# LinTempCont_4ch_V1_0.net
KiCad netlist of a schematic drawn in EAGLE
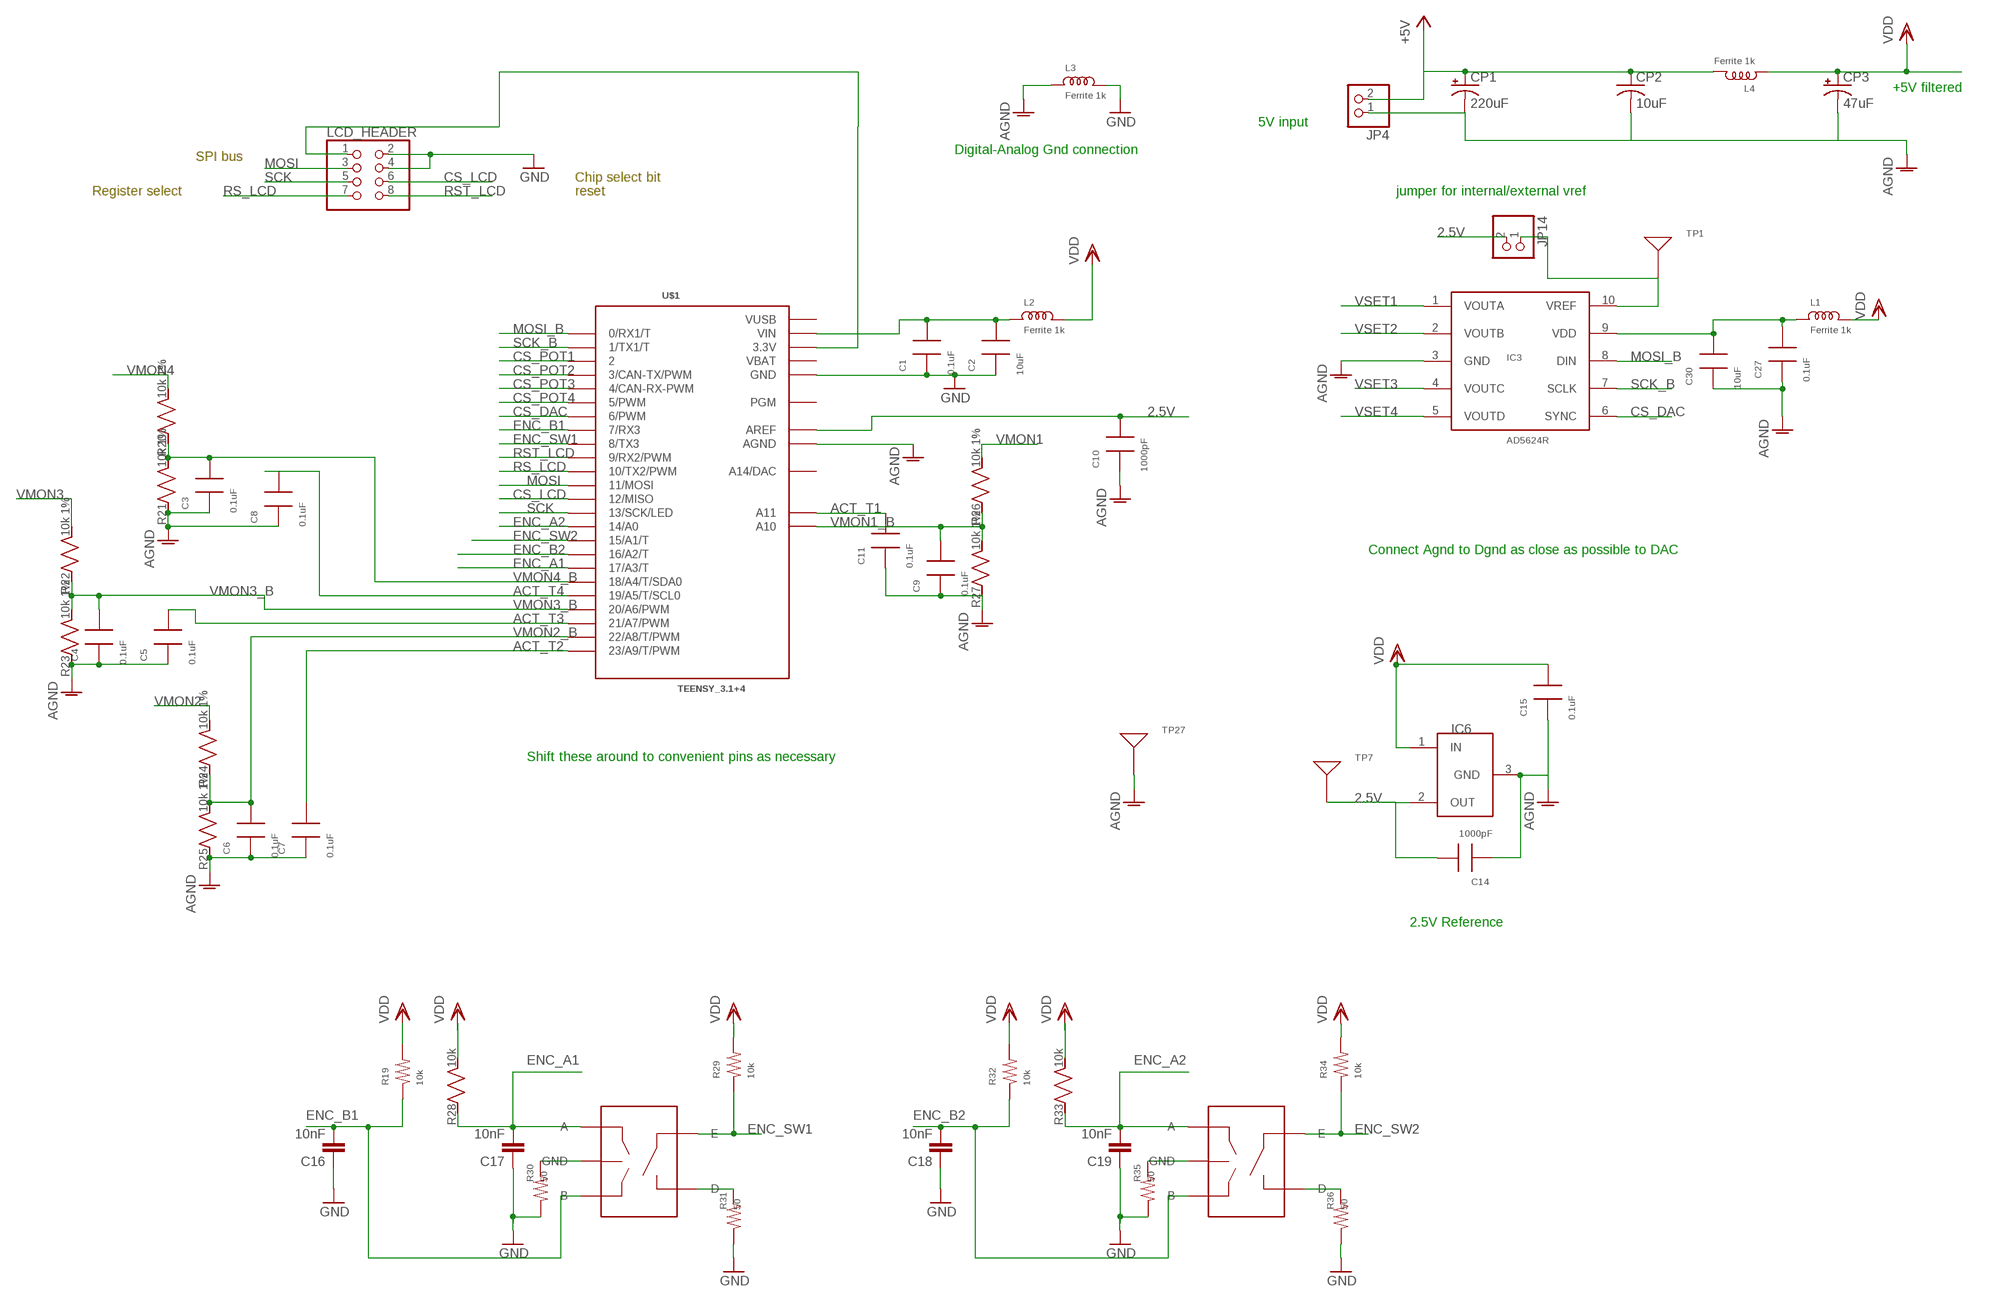
[diagram p0: schematic, sheet 1]
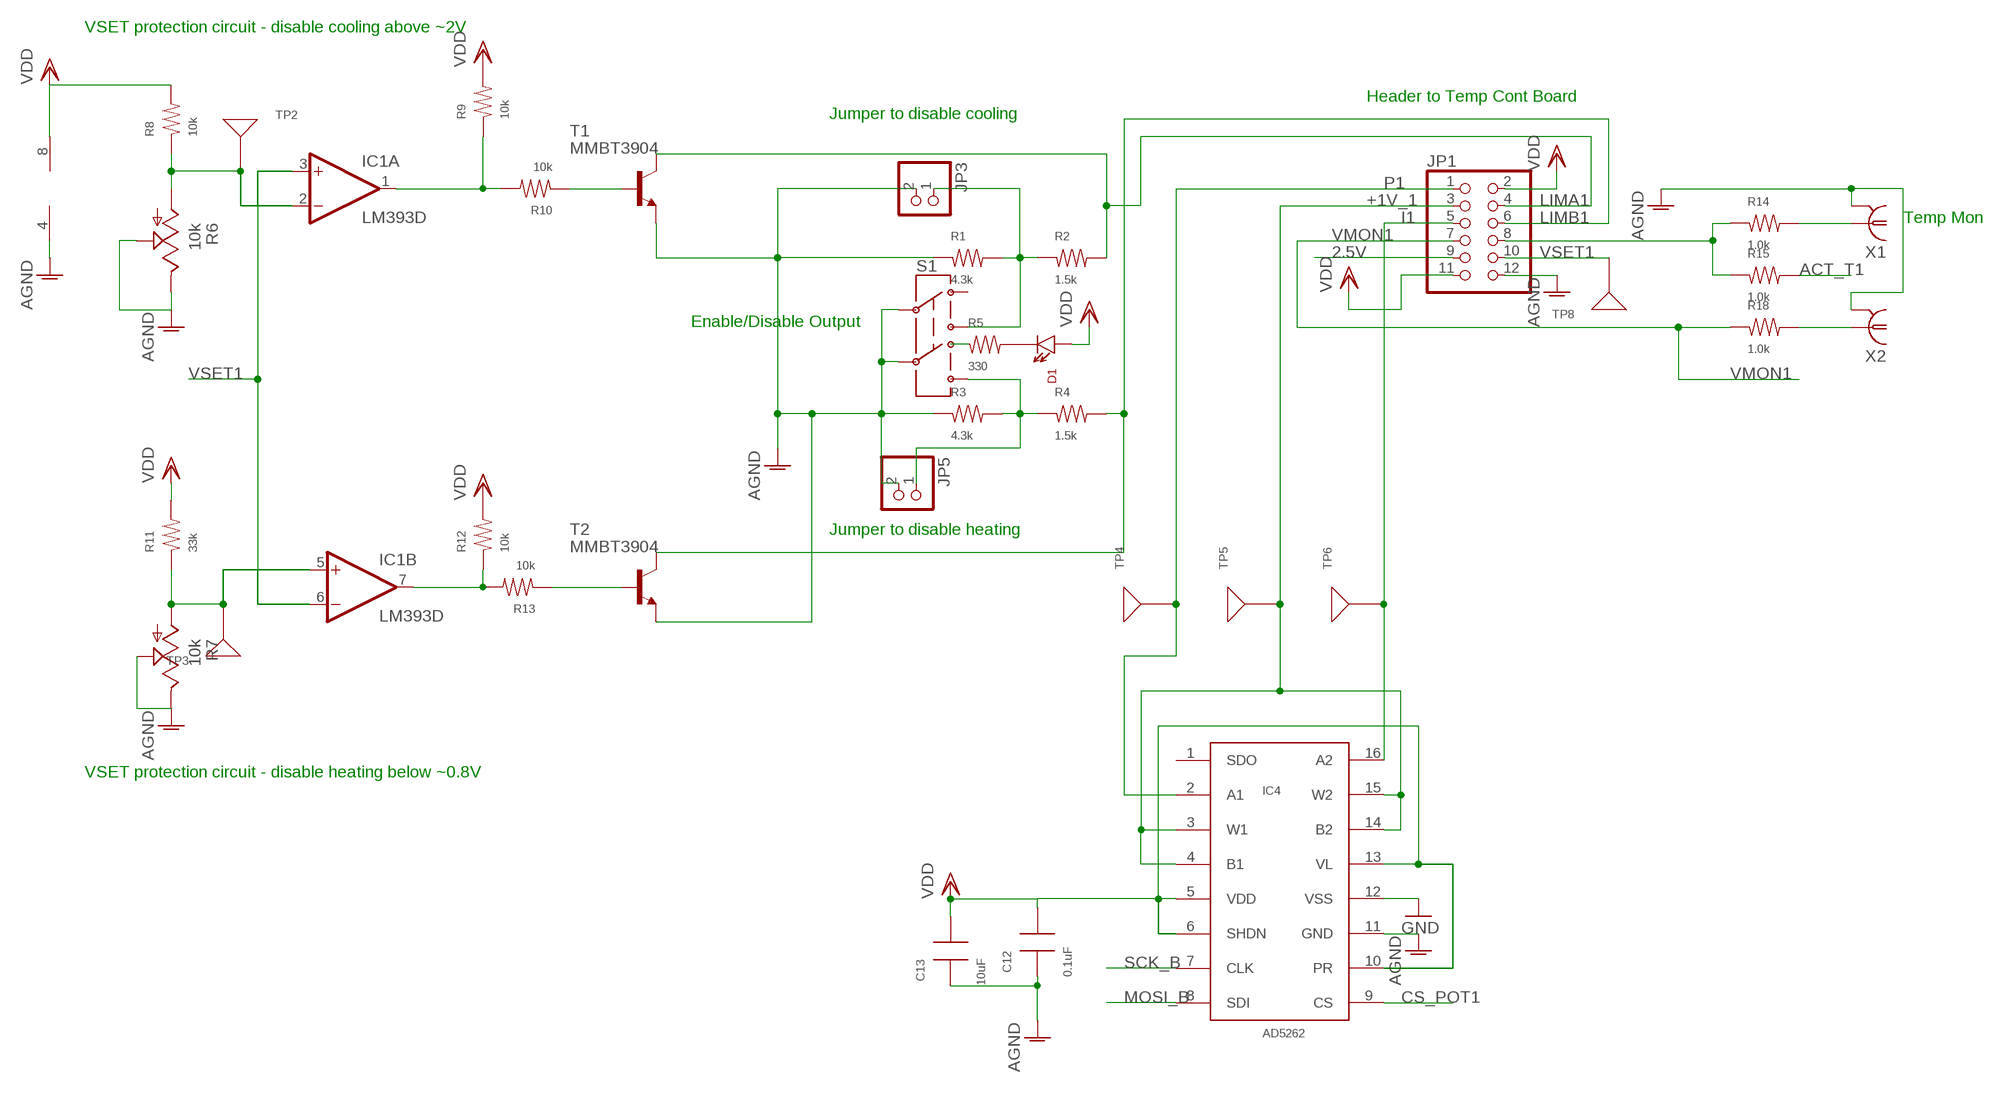
[diagram p1: schematic, sheet 2]
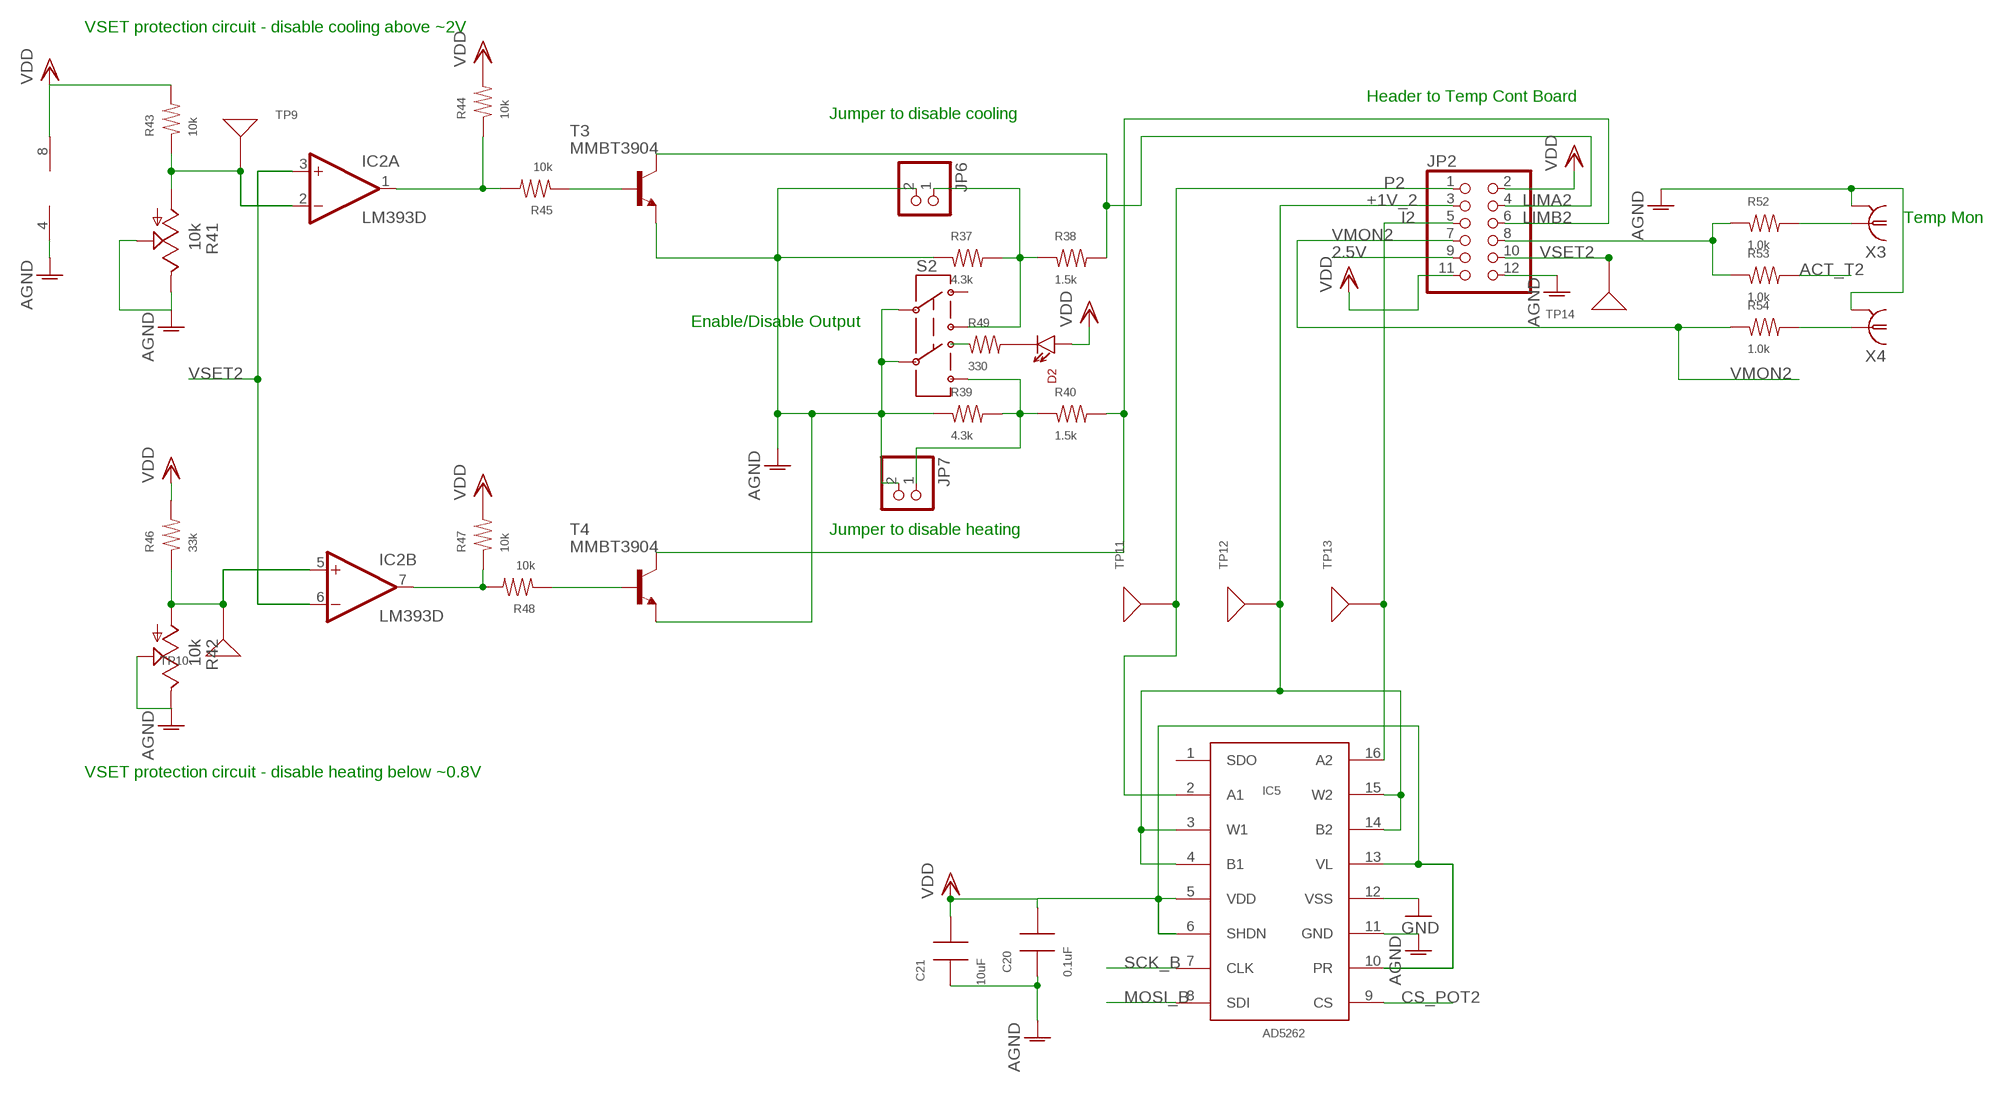
[diagram p2: schematic, sheet 3]
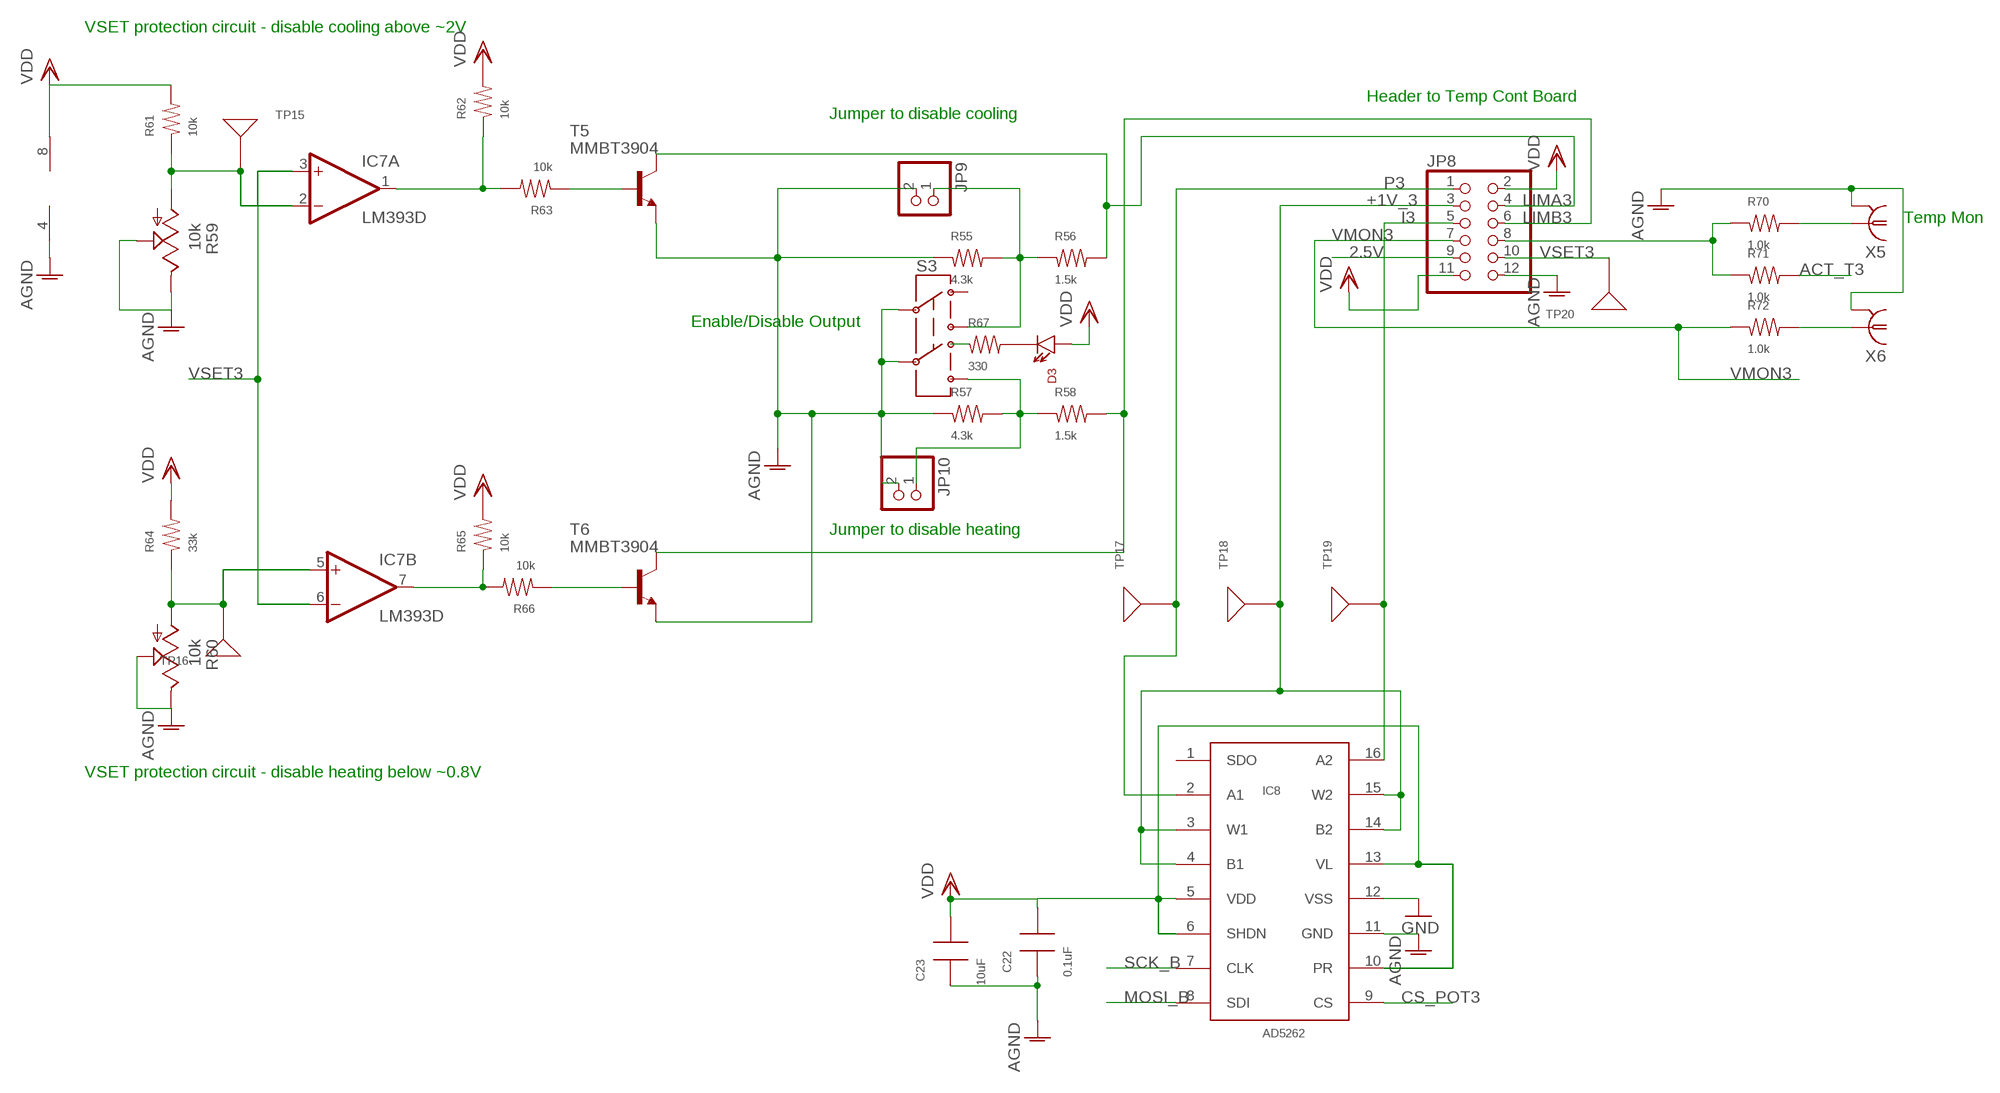
[diagram p3: schematic, sheet 4]
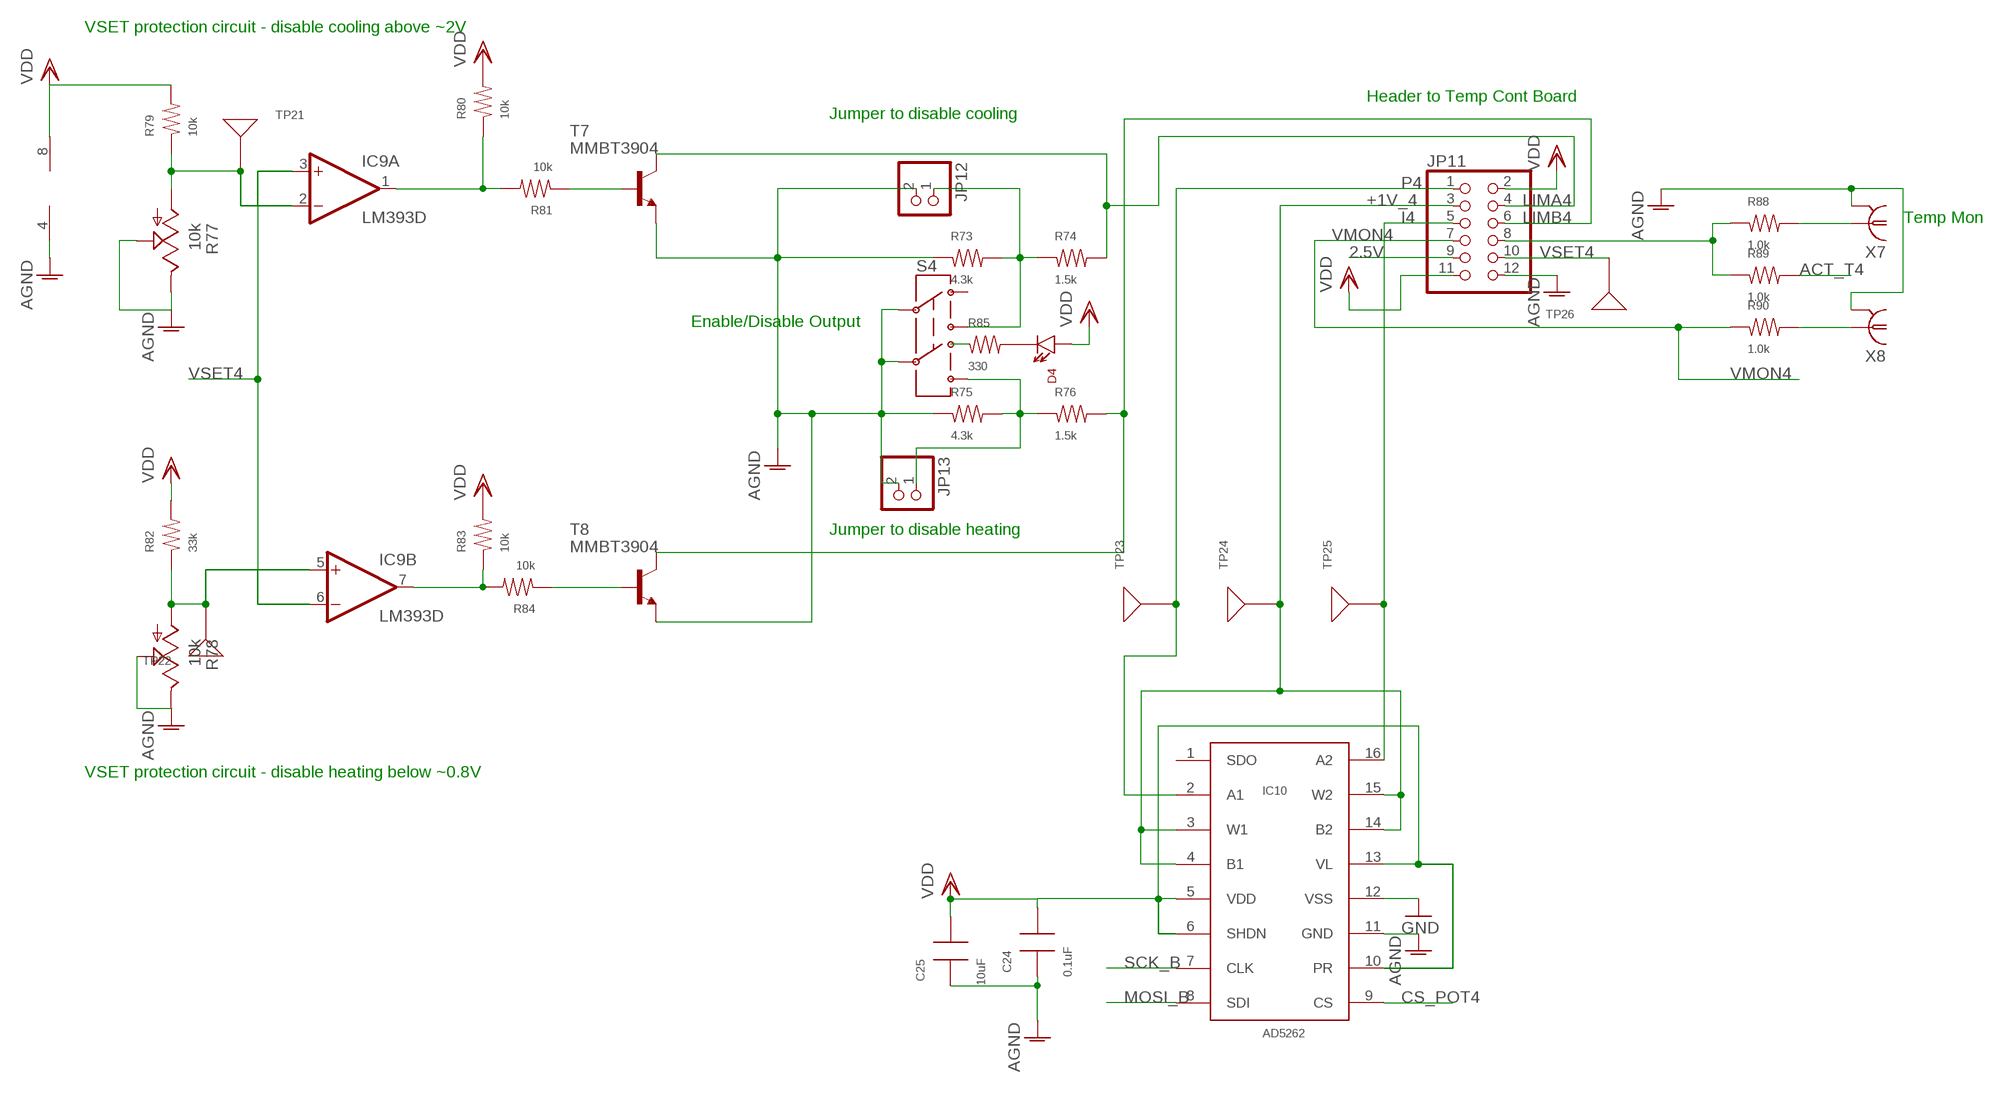
[diagram p4: schematic, sheet 5]

(export (version "E")
  (design (tool "Eeschema 10.0.6"))
  (components
    (comp (ref "C20")
      (value "0.1uF")
      (footprint "eagle-import:0603")
      (libsource (lib "eagle-import") (part "CAP0603"))
    )
    (comp (ref "C21")
      (value "10uF")
      (footprint "eagle-import:0805")
      (libsource (lib "eagle-import") (part "CAP0805"))
    )
    (comp (ref "D2")
      (value "LED/MINI-IND")
      (footprint "eagle-import:HLMP--F0010")
      (libsource (lib "eagle-import") (part "LED/MINI-IND"))
    )
    (comp (ref "IC2")
      (value "LM393D")
      (footprint "eagle-import:SO08")
      (libsource (lib "eagle-import") (part "LM393D"))
    )
    (comp (ref "IC5")
      (value "AD5262")
      (footprint "eagle-import:TSSOP16")
      (libsource (lib "eagle-import") (part "AD5262"))
    )
    (comp (ref "JP2")
      (value "PINHD-2X6/90")
      (footprint "eagle-import:2X06_90")
      (libsource (lib "eagle-import") (part "PINHD-2X6/90"))
    )
    (comp (ref "JP6")
      (value "PINHD-1X2")
      (footprint "eagle-import:1X02")
      (libsource (lib "eagle-import") (part "PINHD-1X2"))
    )
    (comp (ref "JP7")
      (value "PINHD-1X2")
      (footprint "eagle-import:1X02")
      (libsource (lib "eagle-import") (part "PINHD-1X2"))
    )
    (comp (ref "R37")
      (value "4.3k")
      (footprint "eagle-import:0603")
      (libsource (lib "eagle-import") (part "RES0603"))
    )
    (comp (ref "R38")
      (value "1.5k")
      (footprint "eagle-import:0603")
      (libsource (lib "eagle-import") (part "RES0603"))
    )
    (comp (ref "R39")
      (value "4.3k")
      (footprint "eagle-import:0603")
      (libsource (lib "eagle-import") (part "RES0603"))
    )
    (comp (ref "R40")
      (value "1.5k")
      (footprint "eagle-import:0603")
      (libsource (lib "eagle-import") (part "RES0603"))
    )
    (comp (ref "R41")
      (value "10k")
      (footprint "eagle-import:64WPOT")
      (libsource (lib "eagle-import") (part "MODEL64_TRIMPOT/TOP-ADJ"))
    )
    (comp (ref "R42")
      (value "10k")
      (footprint "eagle-import:64WPOT")
      (libsource (lib "eagle-import") (part "MODEL64_TRIMPOT/TOP-ADJ"))
    )
    (comp (ref "R43")
      (value "10k")
      (footprint "eagle-import:0603")
      (libsource (lib "eagle-import") (part "RES0603"))
    )
    (comp (ref "R44")
      (value "10k")
      (footprint "eagle-import:0603")
      (libsource (lib "eagle-import") (part "RES0603"))
    )
    (comp (ref "R45")
      (value "10k")
      (footprint "eagle-import:0603")
      (libsource (lib "eagle-import") (part "RES0603"))
    )
    (comp (ref "R46")
      (value "33k")
      (footprint "eagle-import:0603")
      (libsource (lib "eagle-import") (part "RES0603"))
    )
    (comp (ref "R47")
      (value "10k")
      (footprint "eagle-import:0603")
      (libsource (lib "eagle-import") (part "RES0603"))
    )
    (comp (ref "R48")
      (value "10k")
      (footprint "eagle-import:0603")
      (libsource (lib "eagle-import") (part "RES0603"))
    )
    (comp (ref "R49")
      (value "330")
      (footprint "eagle-import:0603")
      (libsource (lib "eagle-import") (part "RES0603"))
    )
    (comp (ref "R52")
      (value "1.0k")
      (footprint "eagle-import:0603")
      (libsource (lib "eagle-import") (part "RES0603"))
    )
    (comp (ref "R53")
      (value "1.0k")
      (footprint "eagle-import:0603")
      (libsource (lib "eagle-import") (part "RES0603"))
    )
    (comp (ref "R54")
      (value "1.0k")
      (footprint "eagle-import:0603")
      (libsource (lib "eagle-import") (part "RES0603"))
    )
    (comp (ref "S2")
      (value "SWITCH-DPDT/VER")
      (footprint "eagle-import:E-SWITCH-100-M7")
      (libsource (lib "eagle-import") (part "SWITCH-DPDT/VER"))
    )
    (comp (ref "T3")
      (value "MMBT3904")
      (footprint "eagle-import:SOT-23")
      (libsource (lib "eagle-import") (part "MMBT3904"))
    )
    (comp (ref "T4")
      (value "MMBT3904")
      (footprint "eagle-import:SOT-23")
      (libsource (lib "eagle-import") (part "MMBT3904"))
    )
    (comp (ref "TP9")
      (value "TESTPT")
      (footprint "eagle-import:1206TESTPAD")
      (libsource (lib "eagle-import") (part "TESTPT"))
    )
    (comp (ref "TP10")
      (value "TESTPT")
      (footprint "eagle-import:1206TESTPAD")
      (libsource (lib "eagle-import") (part "TESTPT"))
    )
    (comp (ref "TP11")
      (value "TESTPT")
      (footprint "eagle-import:1206TESTPAD")
      (libsource (lib "eagle-import") (part "TESTPT"))
    )
    (comp (ref "TP12")
      (value "TESTPT")
      (footprint "eagle-import:1206TESTPAD")
      (libsource (lib "eagle-import") (part "TESTPT"))
    )
    (comp (ref "TP13")
      (value "TESTPT")
      (footprint "eagle-import:1206TESTPAD")
      (libsource (lib "eagle-import") (part "TESTPT"))
    )
    (comp (ref "TP14")
      (value "TESTPT")
      (footprint "eagle-import:1206TESTPAD")
      (libsource (lib "eagle-import") (part "TESTPT"))
    )
    (comp (ref "X3")
      (value "BNC-H")
      (footprint "eagle-import:BNC90")
      (libsource (lib "eagle-import") (part "BNC-H"))
    )
    (comp (ref "X4")
      (value "BNC-H")
      (footprint "eagle-import:BNC90")
      (libsource (lib "eagle-import") (part "BNC-H"))
    )
    (comp (ref "C22")
      (value "0.1uF")
      (footprint "eagle-import:0603")
      (libsource (lib "eagle-import") (part "CAP0603"))
    )
    (comp (ref "C23")
      (value "10uF")
      (footprint "eagle-import:0805")
      (libsource (lib "eagle-import") (part "CAP0805"))
    )
    (comp (ref "D3")
      (value "LED/MINI-IND")
      (footprint "eagle-import:HLMP--F0010")
      (libsource (lib "eagle-import") (part "LED/MINI-IND"))
    )
    (comp (ref "IC7")
      (value "LM393D")
      (footprint "eagle-import:SO08")
      (libsource (lib "eagle-import") (part "LM393D"))
    )
    (comp (ref "IC8")
      (value "AD5262")
      (footprint "eagle-import:TSSOP16")
      (libsource (lib "eagle-import") (part "AD5262"))
    )
    (comp (ref "JP8")
      (value "PINHD-2X6/90")
      (footprint "eagle-import:2X06_90")
      (libsource (lib "eagle-import") (part "PINHD-2X6/90"))
    )
    (comp (ref "JP9")
      (value "PINHD-1X2")
      (footprint "eagle-import:1X02")
      (libsource (lib "eagle-import") (part "PINHD-1X2"))
    )
    (comp (ref "JP10")
      (value "PINHD-1X2")
      (footprint "eagle-import:1X02")
      (libsource (lib "eagle-import") (part "PINHD-1X2"))
    )
    (comp (ref "R55")
      (value "4.3k")
      (footprint "eagle-import:0603")
      (libsource (lib "eagle-import") (part "RES0603"))
    )
    (comp (ref "R56")
      (value "1.5k")
      (footprint "eagle-import:0603")
      (libsource (lib "eagle-import") (part "RES0603"))
    )
    (comp (ref "R57")
      (value "4.3k")
      (footprint "eagle-import:0603")
      (libsource (lib "eagle-import") (part "RES0603"))
    )
    (comp (ref "R58")
      (value "1.5k")
      (footprint "eagle-import:0603")
      (libsource (lib "eagle-import") (part "RES0603"))
    )
    (comp (ref "R59")
      (value "10k")
      (footprint "eagle-import:64WPOT")
      (libsource (lib "eagle-import") (part "MODEL64_TRIMPOT/TOP-ADJ"))
    )
    (comp (ref "R60")
      (value "10k")
      (footprint "eagle-import:64WPOT")
      (libsource (lib "eagle-import") (part "MODEL64_TRIMPOT/TOP-ADJ"))
    )
    (comp (ref "R61")
      (value "10k")
      (footprint "eagle-import:0603")
      (libsource (lib "eagle-import") (part "RES0603"))
    )
    (comp (ref "R62")
      (value "10k")
      (footprint "eagle-import:0603")
      (libsource (lib "eagle-import") (part "RES0603"))
    )
    (comp (ref "R63")
      (value "10k")
      (footprint "eagle-import:0603")
      (libsource (lib "eagle-import") (part "RES0603"))
    )
    (comp (ref "R64")
      (value "33k")
      (footprint "eagle-import:0603")
      (libsource (lib "eagle-import") (part "RES0603"))
    )
    (comp (ref "R65")
      (value "10k")
      (footprint "eagle-import:0603")
      (libsource (lib "eagle-import") (part "RES0603"))
    )
    (comp (ref "R66")
      (value "10k")
      (footprint "eagle-import:0603")
      (libsource (lib "eagle-import") (part "RES0603"))
    )
    (comp (ref "R67")
      (value "330")
      (footprint "eagle-import:0603")
      (libsource (lib "eagle-import") (part "RES0603"))
    )
    (comp (ref "R70")
      (value "1.0k")
      (footprint "eagle-import:0603")
      (libsource (lib "eagle-import") (part "RES0603"))
    )
    (comp (ref "R71")
      (value "1.0k")
      (footprint "eagle-import:0603")
      (libsource (lib "eagle-import") (part "RES0603"))
    )
    (comp (ref "R72")
      (value "1.0k")
      (footprint "eagle-import:0603")
      (libsource (lib "eagle-import") (part "RES0603"))
    )
    (comp (ref "S3")
      (value "SWITCH-DPDT/VER")
      (footprint "eagle-import:E-SWITCH-100-M7")
      (libsource (lib "eagle-import") (part "SWITCH-DPDT/VER"))
    )
    (comp (ref "T5")
      (value "MMBT3904")
      (footprint "eagle-import:SOT-23")
      (libsource (lib "eagle-import") (part "MMBT3904"))
    )
    (comp (ref "T6")
      (value "MMBT3904")
      (footprint "eagle-import:SOT-23")
      (libsource (lib "eagle-import") (part "MMBT3904"))
    )
    (comp (ref "TP15")
      (value "TESTPT")
      (footprint "eagle-import:1206TESTPAD")
      (libsource (lib "eagle-import") (part "TESTPT"))
    )
    (comp (ref "TP16")
      (value "TESTPT")
      (footprint "eagle-import:1206TESTPAD")
      (libsource (lib "eagle-import") (part "TESTPT"))
    )
    (comp (ref "TP17")
      (value "TESTPT")
      (footprint "eagle-import:1206TESTPAD")
      (libsource (lib "eagle-import") (part "TESTPT"))
    )
    (comp (ref "TP18")
      (value "TESTPT")
      (footprint "eagle-import:1206TESTPAD")
      (libsource (lib "eagle-import") (part "TESTPT"))
    )
    (comp (ref "TP19")
      (value "TESTPT")
      (footprint "eagle-import:1206TESTPAD")
      (libsource (lib "eagle-import") (part "TESTPT"))
    )
    (comp (ref "TP20")
      (value "TESTPT")
      (footprint "eagle-import:1206TESTPAD")
      (libsource (lib "eagle-import") (part "TESTPT"))
    )
    (comp (ref "X5")
      (value "BNC-H")
      (footprint "eagle-import:BNC90")
      (libsource (lib "eagle-import") (part "BNC-H"))
    )
    (comp (ref "X6")
      (value "BNC-H")
      (footprint "eagle-import:BNC90")
      (libsource (lib "eagle-import") (part "BNC-H"))
    )
    (comp (ref "C1")
      (value "0.1uF")
      (footprint "eagle-import:0603")
      (libsource (lib "eagle-import") (part "CAP0603"))
    )
    (comp (ref "C2")
      (value "10uF")
      (footprint "eagle-import:0805")
      (libsource (lib "eagle-import") (part "CAP0805"))
    )
    (comp (ref "C3")
      (value "0.1uF")
      (footprint "eagle-import:0603")
      (libsource (lib "eagle-import") (part "CAP0603"))
    )
    (comp (ref "C4")
      (value "0.1uF")
      (footprint "eagle-import:0603")
      (libsource (lib "eagle-import") (part "CAP0603"))
    )
    (comp (ref "C5")
      (value "0.1uF")
      (footprint "eagle-import:0603")
      (libsource (lib "eagle-import") (part "CAP0603"))
    )
    (comp (ref "C6")
      (value "0.1uF")
      (footprint "eagle-import:0603")
      (libsource (lib "eagle-import") (part "CAP0603"))
    )
    (comp (ref "C7")
      (value "0.1uF")
      (footprint "eagle-import:0603")
      (libsource (lib "eagle-import") (part "CAP0603"))
    )
    (comp (ref "C8")
      (value "0.1uF")
      (footprint "eagle-import:0603")
      (libsource (lib "eagle-import") (part "CAP0603"))
    )
    (comp (ref "C9")
      (value "0.1uF")
      (footprint "eagle-import:0603")
      (libsource (lib "eagle-import") (part "CAP0603"))
    )
    (comp (ref "C10")
      (value "1000pF")
      (footprint "eagle-import:0603")
      (libsource (lib "eagle-import") (part "CAP0603"))
    )
    (comp (ref "C11")
      (value "0.1uF")
      (footprint "eagle-import:0603")
      (libsource (lib "eagle-import") (part "CAP0603"))
    )
    (comp (ref "C14")
      (value "1000pF")
      (footprint "eagle-import:0603")
      (libsource (lib "eagle-import") (part "CAP0603"))
    )
    (comp (ref "C15")
      (value "0.1uF")
      (footprint "eagle-import:0603")
      (libsource (lib "eagle-import") (part "CAP0603"))
    )
    (comp (ref "C16")
      (value "10nF")
      (footprint "eagle-import:C0603")
      (libsource (lib "eagle-import") (part "C-EUC0603"))
    )
    (comp (ref "C17")
      (value "10nF")
      (footprint "eagle-import:C0603")
      (libsource (lib "eagle-import") (part "C-EUC0603"))
    )
    (comp (ref "C18")
      (value "10nF")
      (footprint "eagle-import:C0603")
      (libsource (lib "eagle-import") (part "C-EUC0603"))
    )
    (comp (ref "C19")
      (value "10nF")
      (footprint "eagle-import:C0603")
      (libsource (lib "eagle-import") (part "C-EUC0603"))
    )
    (comp (ref "C27")
      (value "0.1uF")
      (footprint "eagle-import:0603")
      (libsource (lib "eagle-import") (part "CAP0603"))
    )
    (comp (ref "C30")
      (value "10uF")
      (footprint "eagle-import:0805")
      (libsource (lib "eagle-import") (part "CAP0805"))
    )
    (comp (ref "CP1")
      (value "220uF")
      (footprint "eagle-import:PANASONIC_F")
      (libsource (lib "eagle-import") (part "CPOL-USF"))
    )
    (comp (ref "CP2")
      (value "10uF")
      (footprint "eagle-import:C0805K")
      (libsource (lib "eagle-import") (part "C-USC0805K"))
    )
    (comp (ref "CP3")
      (value "47uF")
      (footprint "eagle-import:CT7343")
      (libsource (lib "eagle-import") (part "CPOL-USCT7343"))
    )
    (comp (ref "ENC1")
      (value "PEC09")
      (footprint "eagle-import:PEC092320FS")
      (libsource (lib "eagle-import") (part "PEC09"))
    )
    (comp (ref "ENC2")
      (value "PEC09")
      (footprint "eagle-import:PEC092320FS")
      (libsource (lib "eagle-import") (part "PEC09"))
    )
    (comp (ref "IC3")
      (value "AD5624R")
      (footprint "eagle-import:MSOP10")
      (libsource (lib "eagle-import") (part "AD5624R"))
    )
    (comp (ref "IC6")
      (value "TS6001")
      (footprint "eagle-import:SOT-23")
      (libsource (lib "eagle-import") (part "TS6001"))
    )
    (comp (ref "JP4")
      (value "SCRWTRM-1X2")
      (footprint "eagle-import:1X02_SCRWTRM")
      (libsource (lib "eagle-import") (part "SCRWTRM-1X2"))
    )
    (comp (ref "JP14")
      (value "PINHD-1X2")
      (footprint "eagle-import:1X02")
      (libsource (lib "eagle-import") (part "PINHD-1X2"))
    )
    (comp (ref "L1")
      (value "Ferrite 1k")
      (footprint "eagle-import:0805")
      (libsource (lib "eagle-import") (part "INDUCTOR-0805"))
    )
    (comp (ref "L2")
      (value "Ferrite 1k")
      (footprint "eagle-import:0805")
      (libsource (lib "eagle-import") (part "INDUCTOR-0805"))
    )
    (comp (ref "L3")
      (value "Ferrite 1k")
      (footprint "eagle-import:0805")
      (libsource (lib "eagle-import") (part "INDUCTOR-0805"))
    )
    (comp (ref "L4")
      (value "Ferrite 1k")
      (footprint "eagle-import:0805")
      (libsource (lib "eagle-import") (part "INDUCTOR-0805"))
    )
    (comp (ref "LCD_HEADER")
      (value "PINHD-2X4-SHROUD")
      (footprint "eagle-import:ML08")
      (libsource (lib "eagle-import") (part "PINHD-2X4-SHROUD"))
    )
    (comp (ref "R19")
      (value "10k")
      (footprint "eagle-import:0603")
      (libsource (lib "eagle-import") (part "RES0603"))
    )
    (comp (ref "R20")
      (value "10k 1%")
      (footprint "eagle-import:R_0603")
      (libsource (lib "eagle-import") (part "R_SMDR0603"))
    )
    (comp (ref "R21")
      (value "10k 1%")
      (footprint "eagle-import:R_0603")
      (libsource (lib "eagle-import") (part "R_SMDR0603"))
    )
    (comp (ref "R22")
      (value "10k 1%")
      (footprint "eagle-import:R_0603")
      (libsource (lib "eagle-import") (part "R_SMDR0603"))
    )
    (comp (ref "R23")
      (value "10k 1%")
      (footprint "eagle-import:R_0603")
      (libsource (lib "eagle-import") (part "R_SMDR0603"))
    )
    (comp (ref "R24")
      (value "10k 1%")
      (footprint "eagle-import:R_0603")
      (libsource (lib "eagle-import") (part "R_SMDR0603"))
    )
    (comp (ref "R25")
      (value "10k 1%")
      (footprint "eagle-import:R_0603")
      (libsource (lib "eagle-import") (part "R_SMDR0603"))
    )
    (comp (ref "R26")
      (value "10k 1%")
      (footprint "eagle-import:R_0603")
      (libsource (lib "eagle-import") (part "R_SMDR0603"))
    )
    (comp (ref "R27")
      (value "10k 1%")
      (footprint "eagle-import:R_0603")
      (libsource (lib "eagle-import") (part "R_SMDR0603"))
    )
    (comp (ref "R28")
      (value "10k")
      (footprint "eagle-import:R_0603")
      (libsource (lib "eagle-import") (part "R_SMDR0603"))
    )
    (comp (ref "R29")
      (value "10k")
      (footprint "eagle-import:0603")
      (libsource (lib "eagle-import") (part "RES0603"))
    )
    (comp (ref "R30")
      (value "50")
      (footprint "eagle-import:0603")
      (libsource (lib "eagle-import") (part "RES0603"))
    )
    (comp (ref "R31")
      (value "50")
      (footprint "eagle-import:0603")
      (libsource (lib "eagle-import") (part "RES0603"))
    )
    (comp (ref "R32")
      (value "10k")
      (footprint "eagle-import:0603")
      (libsource (lib "eagle-import") (part "RES0603"))
    )
    (comp (ref "R33")
      (value "10k")
      (footprint "eagle-import:R_0603")
      (libsource (lib "eagle-import") (part "R_SMDR0603"))
    )
    (comp (ref "R34")
      (value "10k")
      (footprint "eagle-import:0603")
      (libsource (lib "eagle-import") (part "RES0603"))
    )
    (comp (ref "R35")
      (value "50")
      (footprint "eagle-import:0603")
      (libsource (lib "eagle-import") (part "RES0603"))
    )
    (comp (ref "R36")
      (value "50")
      (footprint "eagle-import:0603")
      (libsource (lib "eagle-import") (part "RES0603"))
    )
    (comp (ref "TP1")
      (value "TESTPT")
      (footprint "eagle-import:1206TESTPAD")
      (libsource (lib "eagle-import") (part "TESTPT"))
    )
    (comp (ref "TP7")
      (value "TESTPT")
      (footprint "eagle-import:1206TESTPAD")
      (libsource (lib "eagle-import") (part "TESTPT"))
    )
    (comp (ref "TP27")
      (value "TESTPT")
      (footprint "eagle-import:1206TESTPAD")
      (libsource (lib "eagle-import") (part "TESTPT"))
    )
    (comp (ref "U$1")
      (value "TEENSY_3.1+4")
      (footprint "eagle-import:TEENSY_3.1+4")
      (libsource (lib "eagle-import") (part "TEENSY_3.1+4"))
    )
    (comp (ref "C12")
      (value "0.1uF")
      (footprint "eagle-import:0603")
      (libsource (lib "eagle-import") (part "CAP0603"))
    )
    (comp (ref "C13")
      (value "10uF")
      (footprint "eagle-import:0805")
      (libsource (lib "eagle-import") (part "CAP0805"))
    )
    (comp (ref "D1")
      (value "LED/MINI-IND")
      (footprint "eagle-import:HLMP--F0010")
      (libsource (lib "eagle-import") (part "LED/MINI-IND"))
    )
    (comp (ref "IC1")
      (value "LM393D")
      (footprint "eagle-import:SO08")
      (libsource (lib "eagle-import") (part "LM393D"))
    )
    (comp (ref "IC4")
      (value "AD5262")
      (footprint "eagle-import:TSSOP16")
      (libsource (lib "eagle-import") (part "AD5262"))
    )
    (comp (ref "JP1")
      (value "PINHD-2X6/90")
      (footprint "eagle-import:2X06_90")
      (libsource (lib "eagle-import") (part "PINHD-2X6/90"))
    )
    (comp (ref "JP3")
      (value "PINHD-1X2")
      (footprint "eagle-import:1X02")
      (libsource (lib "eagle-import") (part "PINHD-1X2"))
    )
    (comp (ref "JP5")
      (value "PINHD-1X2")
      (footprint "eagle-import:1X02")
      (libsource (lib "eagle-import") (part "PINHD-1X2"))
    )
    (comp (ref "R1")
      (value "4.3k")
      (footprint "eagle-import:0603")
      (libsource (lib "eagle-import") (part "RES0603"))
    )
    (comp (ref "R2")
      (value "1.5k")
      (footprint "eagle-import:0603")
      (libsource (lib "eagle-import") (part "RES0603"))
    )
    (comp (ref "R3")
      (value "4.3k")
      (footprint "eagle-import:0603")
      (libsource (lib "eagle-import") (part "RES0603"))
    )
    (comp (ref "R4")
      (value "1.5k")
      (footprint "eagle-import:0603")
      (libsource (lib "eagle-import") (part "RES0603"))
    )
    (comp (ref "R5")
      (value "330")
      (footprint "eagle-import:0603")
      (libsource (lib "eagle-import") (part "RES0603"))
    )
    (comp (ref "R6")
      (value "10k")
      (footprint "eagle-import:64WPOT")
      (libsource (lib "eagle-import") (part "MODEL64_TRIMPOT/TOP-ADJ"))
    )
    (comp (ref "R7")
      (value "10k")
      (footprint "eagle-import:64WPOT")
      (libsource (lib "eagle-import") (part "MODEL64_TRIMPOT/TOP-ADJ"))
    )
    (comp (ref "R8")
      (value "10k")
      (footprint "eagle-import:0603")
      (libsource (lib "eagle-import") (part "RES0603"))
    )
    (comp (ref "R9")
      (value "10k")
      (footprint "eagle-import:0603")
      (libsource (lib "eagle-import") (part "RES0603"))
    )
    (comp (ref "R10")
      (value "10k")
      (footprint "eagle-import:0603")
      (libsource (lib "eagle-import") (part "RES0603"))
    )
    (comp (ref "R11")
      (value "33k")
      (footprint "eagle-import:0603")
      (libsource (lib "eagle-import") (part "RES0603"))
    )
    (comp (ref "R12")
      (value "10k")
      (footprint "eagle-import:0603")
      (libsource (lib "eagle-import") (part "RES0603"))
    )
    (comp (ref "R13")
      (value "10k")
      (footprint "eagle-import:0603")
      (libsource (lib "eagle-import") (part "RES0603"))
    )
    (comp (ref "R14")
      (value "1.0k")
      (footprint "eagle-import:0603")
      (libsource (lib "eagle-import") (part "RES0603"))
    )
    (comp (ref "R15")
      (value "1.0k")
      (footprint "eagle-import:0603")
      (libsource (lib "eagle-import") (part "RES0603"))
    )
    (comp (ref "R18")
      (value "1.0k")
      (footprint "eagle-import:0603")
      (libsource (lib "eagle-import") (part "RES0603"))
    )
    (comp (ref "S1")
      (value "SWITCH-DPDT/VER")
      (footprint "eagle-import:E-SWITCH-100-M7")
      (libsource (lib "eagle-import") (part "SWITCH-DPDT/VER"))
    )
    (comp (ref "T1")
      (value "MMBT3904")
      (footprint "eagle-import:SOT-23")
      (libsource (lib "eagle-import") (part "MMBT3904"))
    )
    (comp (ref "T2")
      (value "MMBT3904")
      (footprint "eagle-import:SOT-23")
      (libsource (lib "eagle-import") (part "MMBT3904"))
    )
    (comp (ref "TP2")
      (value "TESTPT")
      (footprint "eagle-import:1206TESTPAD")
      (libsource (lib "eagle-import") (part "TESTPT"))
    )
    (comp (ref "TP3")
      (value "TESTPT")
      (footprint "eagle-import:1206TESTPAD")
      (libsource (lib "eagle-import") (part "TESTPT"))
    )
    (comp (ref "TP4")
      (value "TESTPT")
      (footprint "eagle-import:1206TESTPAD")
      (libsource (lib "eagle-import") (part "TESTPT"))
    )
    (comp (ref "TP5")
      (value "TESTPT")
      (footprint "eagle-import:1206TESTPAD")
      (libsource (lib "eagle-import") (part "TESTPT"))
    )
    (comp (ref "TP6")
      (value "TESTPT")
      (footprint "eagle-import:1206TESTPAD")
      (libsource (lib "eagle-import") (part "TESTPT"))
    )
    (comp (ref "TP8")
      (value "TESTPT")
      (footprint "eagle-import:1206TESTPAD")
      (libsource (lib "eagle-import") (part "TESTPT"))
    )
    (comp (ref "X1")
      (value "BNC-H")
      (footprint "eagle-import:BNC90")
      (libsource (lib "eagle-import") (part "BNC-H"))
    )
    (comp (ref "X2")
      (value "BNC-H")
      (footprint "eagle-import:BNC90")
      (libsource (lib "eagle-import") (part "BNC-H"))
    )
    (comp (ref "C24")
      (value "0.1uF")
      (footprint "eagle-import:0603")
      (libsource (lib "eagle-import") (part "CAP0603"))
    )
    (comp (ref "C25")
      (value "10uF")
      (footprint "eagle-import:0805")
      (libsource (lib "eagle-import") (part "CAP0805"))
    )
    (comp (ref "D4")
      (value "LED/MINI-IND")
      (footprint "eagle-import:HLMP--F0010")
      (libsource (lib "eagle-import") (part "LED/MINI-IND"))
    )
    (comp (ref "IC9")
      (value "LM393D")
      (footprint "eagle-import:SO08")
      (libsource (lib "eagle-import") (part "LM393D"))
    )
    (comp (ref "IC10")
      (value "AD5262")
      (footprint "eagle-import:TSSOP16")
      (libsource (lib "eagle-import") (part "AD5262"))
    )
    (comp (ref "JP11")
      (value "PINHD-2X6/90")
      (footprint "eagle-import:2X06_90")
      (libsource (lib "eagle-import") (part "PINHD-2X6/90"))
    )
    (comp (ref "JP12")
      (value "PINHD-1X2")
      (footprint "eagle-import:1X02")
      (libsource (lib "eagle-import") (part "PINHD-1X2"))
    )
    (comp (ref "JP13")
      (value "PINHD-1X2")
      (footprint "eagle-import:1X02")
      (libsource (lib "eagle-import") (part "PINHD-1X2"))
    )
    (comp (ref "R73")
      (value "4.3k")
      (footprint "eagle-import:0603")
      (libsource (lib "eagle-import") (part "RES0603"))
    )
    (comp (ref "R74")
      (value "1.5k")
      (footprint "eagle-import:0603")
      (libsource (lib "eagle-import") (part "RES0603"))
    )
    (comp (ref "R75")
      (value "4.3k")
      (footprint "eagle-import:0603")
      (libsource (lib "eagle-import") (part "RES0603"))
    )
    (comp (ref "R76")
      (value "1.5k")
      (footprint "eagle-import:0603")
      (libsource (lib "eagle-import") (part "RES0603"))
    )
    (comp (ref "R77")
      (value "10k")
      (footprint "eagle-import:64WPOT")
      (libsource (lib "eagle-import") (part "MODEL64_TRIMPOT/TOP-ADJ"))
    )
    (comp (ref "R78")
      (value "10k")
      (footprint "eagle-import:64WPOT")
      (libsource (lib "eagle-import") (part "MODEL64_TRIMPOT/TOP-ADJ"))
    )
    (comp (ref "R79")
      (value "10k")
      (footprint "eagle-import:0603")
      (libsource (lib "eagle-import") (part "RES0603"))
    )
    (comp (ref "R80")
      (value "10k")
      (footprint "eagle-import:0603")
      (libsource (lib "eagle-import") (part "RES0603"))
    )
    (comp (ref "R81")
      (value "10k")
      (footprint "eagle-import:0603")
      (libsource (lib "eagle-import") (part "RES0603"))
    )
    (comp (ref "R82")
      (value "33k")
      (footprint "eagle-import:0603")
      (libsource (lib "eagle-import") (part "RES0603"))
    )
    (comp (ref "R83")
      (value "10k")
      (footprint "eagle-import:0603")
      (libsource (lib "eagle-import") (part "RES0603"))
    )
    (comp (ref "R84")
      (value "10k")
      (footprint "eagle-import:0603")
      (libsource (lib "eagle-import") (part "RES0603"))
    )
    (comp (ref "R85")
      (value "330")
      (footprint "eagle-import:0603")
      (libsource (lib "eagle-import") (part "RES0603"))
    )
    (comp (ref "R88")
      (value "1.0k")
      (footprint "eagle-import:0603")
      (libsource (lib "eagle-import") (part "RES0603"))
    )
    (comp (ref "R89")
      (value "1.0k")
      (footprint "eagle-import:0603")
      (libsource (lib "eagle-import") (part "RES0603"))
    )
    (comp (ref "R90")
      (value "1.0k")
      (footprint "eagle-import:0603")
      (libsource (lib "eagle-import") (part "RES0603"))
    )
    (comp (ref "S4")
      (value "SWITCH-DPDT/VER")
      (footprint "eagle-import:E-SWITCH-100-M7")
      (libsource (lib "eagle-import") (part "SWITCH-DPDT/VER"))
    )
    (comp (ref "T7")
      (value "MMBT3904")
      (footprint "eagle-import:SOT-23")
      (libsource (lib "eagle-import") (part "MMBT3904"))
    )
    (comp (ref "T8")
      (value "MMBT3904")
      (footprint "eagle-import:SOT-23")
      (libsource (lib "eagle-import") (part "MMBT3904"))
    )
    (comp (ref "TP21")
      (value "TESTPT")
      (footprint "eagle-import:1206TESTPAD")
      (libsource (lib "eagle-import") (part "TESTPT"))
    )
    (comp (ref "TP22")
      (value "TESTPT")
      (footprint "eagle-import:1206TESTPAD")
      (libsource (lib "eagle-import") (part "TESTPT"))
    )
    (comp (ref "TP23")
      (value "TESTPT")
      (footprint "eagle-import:1206TESTPAD")
      (libsource (lib "eagle-import") (part "TESTPT"))
    )
    (comp (ref "TP24")
      (value "TESTPT")
      (footprint "eagle-import:1206TESTPAD")
      (libsource (lib "eagle-import") (part "TESTPT"))
    )
    (comp (ref "TP25")
      (value "TESTPT")
      (footprint "eagle-import:1206TESTPAD")
      (libsource (lib "eagle-import") (part "TESTPT"))
    )
    (comp (ref "TP26")
      (value "TESTPT")
      (footprint "eagle-import:1206TESTPAD")
      (libsource (lib "eagle-import") (part "TESTPT"))
    )
    (comp (ref "X7")
      (value "BNC-H")
      (footprint "eagle-import:BNC90")
      (libsource (lib "eagle-import") (part "BNC-H"))
    )
    (comp (ref "X8")
      (value "BNC-H")
      (footprint "eagle-import:BNC90")
      (libsource (lib "eagle-import") (part "BNC-H"))
    )
  )
  (nets
    (net (code "1") (name "+1V_1") (class "Default")
      (node (ref "IC4") (pin "14") (pinfunction "B2_14") (pintype "bidirectional"))
      (node (ref "IC4") (pin "15") (pinfunction "W2_15") (pintype "bidirectional"))
      (node (ref "IC4") (pin "3") (pinfunction "W1_3") (pintype "bidirectional"))
      (node (ref "IC4") (pin "4") (pinfunction "B1_4") (pintype "bidirectional"))
      (node (ref "JP1") (pin "3") (pinfunction "3_3") (pintype "passive"))
      (node (ref "TP5") (pin "P$1") (pinfunction "P$1_P$1") (pintype "bidirectional"))
    )
    (net (code "2") (name "+1V_2") (class "Default")
      (node (ref "IC5") (pin "14") (pinfunction "B2_14") (pintype "bidirectional"))
      (node (ref "IC5") (pin "15") (pinfunction "W2_15") (pintype "bidirectional"))
      (node (ref "IC5") (pin "3") (pinfunction "W1_3") (pintype "bidirectional"))
      (node (ref "IC5") (pin "4") (pinfunction "B1_4") (pintype "bidirectional"))
      (node (ref "JP2") (pin "3") (pinfunction "3_3") (pintype "passive"))
      (node (ref "TP12") (pin "P$1") (pinfunction "P$1_P$1") (pintype "bidirectional"))
    )
    (net (code "3") (name "+1V_3") (class "Default")
      (node (ref "IC8") (pin "14") (pinfunction "B2_14") (pintype "bidirectional"))
      (node (ref "IC8") (pin "15") (pinfunction "W2_15") (pintype "bidirectional"))
      (node (ref "IC8") (pin "3") (pinfunction "W1_3") (pintype "bidirectional"))
      (node (ref "IC8") (pin "4") (pinfunction "B1_4") (pintype "bidirectional"))
      (node (ref "JP8") (pin "3") (pinfunction "3_3") (pintype "passive"))
      (node (ref "TP18") (pin "P$1") (pinfunction "P$1_P$1") (pintype "bidirectional"))
    )
    (net (code "4") (name "+1V_4") (class "Default")
      (node (ref "IC10") (pin "14") (pinfunction "B2_14") (pintype "bidirectional"))
      (node (ref "IC10") (pin "15") (pinfunction "W2_15") (pintype "bidirectional"))
      (node (ref "IC10") (pin "3") (pinfunction "W1_3") (pintype "bidirectional"))
      (node (ref "IC10") (pin "4") (pinfunction "B1_4") (pintype "bidirectional"))
      (node (ref "JP11") (pin "3") (pinfunction "3_3") (pintype "passive"))
      (node (ref "TP24") (pin "P$1") (pinfunction "P$1_P$1") (pintype "bidirectional"))
    )
    (net (code "5") (name "+5V") (class "Default")
      (node (ref "CP1") (pin "+") (pinfunction "+_+") (pintype "passive"))
      (node (ref "CP2") (pin "1") (pinfunction "1_1") (pintype "passive"))
      (node (ref "JP4") (pin "2") (pinfunction "2_2") (pintype "passive"))
      (node (ref "L4") (pin "2") (pinfunction "P$2_2") (pintype "passive"))
    )
    (net (code "6") (name "2.5V") (class "Default")
      (node (ref "C10") (pin "2") (pinfunction "P$2_2") (pintype "passive"))
      (node (ref "C14") (pin "2") (pinfunction "P$2_2") (pintype "passive"))
      (node (ref "IC6") (pin "2") (pinfunction "OUT_2") (pintype "bidirectional"))
      (node (ref "JP1") (pin "9") (pinfunction "9_9") (pintype "passive"))
      (node (ref "JP11") (pin "9") (pinfunction "9_9") (pintype "passive"))
      (node (ref "JP14") (pin "2") (pinfunction "2_2") (pintype "passive"))
      (node (ref "JP2") (pin "9") (pinfunction "9_9") (pintype "passive"))
      (node (ref "JP8") (pin "9") (pinfunction "9_9") (pintype "passive"))
      (node (ref "TP7") (pin "P$1") (pinfunction "P$1_P$1") (pintype "bidirectional"))
      (node (ref "U$1") (pin "AREF") (pinfunction "AREF_AREF") (pintype "power_in"))
    )
    (net (code "7") (name "ACT_T1") (class "Default")
      (node (ref "C11") (pin "2") (pinfunction "P$2_2") (pintype "passive"))
      (node (ref "R15") (pin "2") (pinfunction "P$2_2") (pintype "passive"))
      (node (ref "U$1") (pin "A11") (pinfunction "A11_A11") (pintype "bidirectional"))
    )
    (net (code "8") (name "ACT_T2") (class "Default")
      (node (ref "C7") (pin "2") (pinfunction "P$2_2") (pintype "passive"))
      (node (ref "R53") (pin "2") (pinfunction "P$2_2") (pintype "passive"))
      (node (ref "U$1") (pin "23/A9") (pinfunction "23/A9/T/PWM_23/A9") (pintype "bidirectional"))
    )
    (net (code "9") (name "ACT_T3") (class "Default")
      (node (ref "C5") (pin "2") (pinfunction "P$2_2") (pintype "passive"))
      (node (ref "R71") (pin "2") (pinfunction "P$2_2") (pintype "passive"))
      (node (ref "U$1") (pin "21/A7") (pinfunction "21/A7/PWM_21/A7") (pintype "bidirectional"))
    )
    (net (code "10") (name "ACT_T4") (class "Default")
      (node (ref "C8") (pin "2") (pinfunction "P$2_2") (pintype "passive"))
      (node (ref "R89") (pin "2") (pinfunction "P$2_2") (pintype "passive"))
      (node (ref "U$1") (pin "19/A5") (pinfunction "19/A5/T/SCL0_19/A5") (pintype "bidirectional"))
    )
    (net (code "11") (name "AGND") (class "Default")
      (node (ref "C10") (pin "1") (pinfunction "P$1_1") (pintype "passive"))
      (node (ref "C11") (pin "1") (pinfunction "P$1_1") (pintype "passive"))
      (node (ref "C12") (pin "1") (pinfunction "P$1_1") (pintype "passive"))
      (node (ref "C13") (pin "1") (pinfunction "P$1_1") (pintype "passive"))
      (node (ref "C14") (pin "1") (pinfunction "P$1_1") (pintype "passive"))
      (node (ref "C15") (pin "1") (pinfunction "P$1_1") (pintype "passive"))
      (node (ref "C20") (pin "1") (pinfunction "P$1_1") (pintype "passive"))
      (node (ref "C21") (pin "1") (pinfunction "P$1_1") (pintype "passive"))
      (node (ref "C22") (pin "1") (pinfunction "P$1_1") (pintype "passive"))
      (node (ref "C23") (pin "1") (pinfunction "P$1_1") (pintype "passive"))
      (node (ref "C24") (pin "1") (pinfunction "P$1_1") (pintype "passive"))
      (node (ref "C25") (pin "1") (pinfunction "P$1_1") (pintype "passive"))
      (node (ref "C27") (pin "1") (pinfunction "P$1_1") (pintype "passive"))
      (node (ref "C3") (pin "1") (pinfunction "P$1_1") (pintype "passive"))
      (node (ref "C30") (pin "1") (pinfunction "P$1_1") (pintype "passive"))
      (node (ref "C4") (pin "1") (pinfunction "P$1_1") (pintype "passive"))
      (node (ref "C5") (pin "1") (pinfunction "P$1_1") (pintype "passive"))
      (node (ref "C6") (pin "1") (pinfunction "P$1_1") (pintype "passive"))
      (node (ref "C7") (pin "1") (pinfunction "P$1_1") (pintype "passive"))
      (node (ref "C8") (pin "1") (pinfunction "P$1_1") (pintype "passive"))
      (node (ref "C9") (pin "1") (pinfunction "P$1_1") (pintype "passive"))
      (node (ref "CP1") (pin "-") (pinfunction "-_-") (pintype "passive"))
      (node (ref "CP2") (pin "2") (pinfunction "2_2") (pintype "passive"))
      (node (ref "CP3") (pin "-") (pinfunction "-_-") (pintype "passive"))
      (node (ref "IC1") (pin "4") (pinfunction "V-_4") (pintype "power_in"))
      (node (ref "IC10") (pin "11") (pinfunction "GND_11") (pintype "power_in"))
      (node (ref "IC2") (pin "4") (pinfunction "V-_4") (pintype "power_in"))
      (node (ref "IC3") (pin "3") (pinfunction "GND_3") (pintype "power_in"))
      (node (ref "IC4") (pin "11") (pinfunction "GND_11") (pintype "power_in"))
      (node (ref "IC5") (pin "11") (pinfunction "GND_11") (pintype "power_in"))
      (node (ref "IC6") (pin "3") (pinfunction "GND_3") (pintype "bidirectional"))
      (node (ref "IC7") (pin "4") (pinfunction "V-_4") (pintype "power_in"))
      (node (ref "IC8") (pin "11") (pinfunction "GND_11") (pintype "power_in"))
      (node (ref "IC9") (pin "4") (pinfunction "V-_4") (pintype "power_in"))
      (node (ref "JP1") (pin "12") (pinfunction "12_12") (pintype "passive"))
      (node (ref "JP10") (pin "2") (pinfunction "2_2") (pintype "passive"))
      (node (ref "JP11") (pin "12") (pinfunction "12_12") (pintype "passive"))
      (node (ref "JP12") (pin "2") (pinfunction "2_2") (pintype "passive"))
      (node (ref "JP13") (pin "2") (pinfunction "2_2") (pintype "passive"))
      (node (ref "JP2") (pin "12") (pinfunction "12_12") (pintype "passive"))
      (node (ref "JP3") (pin "2") (pinfunction "2_2") (pintype "passive"))
      (node (ref "JP4") (pin "1") (pinfunction "1_1") (pintype "passive"))
      (node (ref "JP5") (pin "2") (pinfunction "2_2") (pintype "passive"))
      (node (ref "JP6") (pin "2") (pinfunction "2_2") (pintype "passive"))
      (node (ref "JP7") (pin "2") (pinfunction "2_2") (pintype "passive"))
      (node (ref "JP8") (pin "12") (pinfunction "12_12") (pintype "passive"))
      (node (ref "JP9") (pin "2") (pinfunction "2_2") (pintype "passive"))
      (node (ref "L3") (pin "1") (pinfunction "P$1_1") (pintype "passive"))
      (node (ref "R1") (pin "1") (pinfunction "P$1_1") (pintype "passive"))
      (node (ref "R21") (pin "P$1") (pinfunction "1_P$1") (pintype "passive"))
      (node (ref "R23") (pin "P$1") (pinfunction "1_P$1") (pintype "passive"))
      (node (ref "R25") (pin "P$1") (pinfunction "1_P$1") (pintype "passive"))
      (node (ref "R27") (pin "P$1") (pinfunction "1_P$1") (pintype "passive"))
      (node (ref "R3") (pin "1") (pinfunction "P$1_1") (pintype "passive"))
      (node (ref "R37") (pin "1") (pinfunction "P$1_1") (pintype "passive"))
      (node (ref "R39") (pin "1") (pinfunction "P$1_1") (pintype "passive"))
      (node (ref "R41") (pin "P$2") (pinfunction "2_P$2") (pintype "passive"))
      (node (ref "R41") (pin "P$3") (pinfunction "3_P$3") (pintype "passive"))
      (node (ref "R42") (pin "P$2") (pinfunction "2_P$2") (pintype "passive"))
      (node (ref "R42") (pin "P$3") (pinfunction "3_P$3") (pintype "passive"))
      (node (ref "R55") (pin "1") (pinfunction "P$1_1") (pintype "passive"))
      (node (ref "R57") (pin "1") (pinfunction "P$1_1") (pintype "passive"))
      (node (ref "R59") (pin "P$2") (pinfunction "2_P$2") (pintype "passive"))
      (node (ref "R59") (pin "P$3") (pinfunction "3_P$3") (pintype "passive"))
      (node (ref "R6") (pin "P$2") (pinfunction "2_P$2") (pintype "passive"))
      (node (ref "R6") (pin "P$3") (pinfunction "3_P$3") (pintype "passive"))
      (node (ref "R60") (pin "P$2") (pinfunction "2_P$2") (pintype "passive"))
      (node (ref "R60") (pin "P$3") (pinfunction "3_P$3") (pintype "passive"))
      (node (ref "R7") (pin "P$2") (pinfunction "2_P$2") (pintype "passive"))
      (node (ref "R7") (pin "P$3") (pinfunction "3_P$3") (pintype "passive"))
      (node (ref "R73") (pin "1") (pinfunction "P$1_1") (pintype "passive"))
      (node (ref "R75") (pin "1") (pinfunction "P$1_1") (pintype "passive"))
      (node (ref "R77") (pin "P$2") (pinfunction "2_P$2") (pintype "passive"))
      (node (ref "R77") (pin "P$3") (pinfunction "3_P$3") (pintype "passive"))
      (node (ref "R78") (pin "P$2") (pinfunction "2_P$2") (pintype "passive"))
      (node (ref "R78") (pin "P$3") (pinfunction "3_P$3") (pintype "passive"))
      (node (ref "S1") (pin "P$2") (pinfunction "2_P$2") (pintype "bidirectional"))
      (node (ref "S1") (pin "P$5") (pinfunction "5_P$5") (pintype "bidirectional"))
      (node (ref "S2") (pin "P$2") (pinfunction "2_P$2") (pintype "bidirectional"))
      (node (ref "S2") (pin "P$5") (pinfunction "5_P$5") (pintype "bidirectional"))
      (node (ref "S3") (pin "P$2") (pinfunction "2_P$2") (pintype "bidirectional"))
      (node (ref "S3") (pin "P$5") (pinfunction "5_P$5") (pintype "bidirectional"))
      (node (ref "S4") (pin "P$2") (pinfunction "2_P$2") (pintype "bidirectional"))
      (node (ref "S4") (pin "P$5") (pinfunction "5_P$5") (pintype "bidirectional"))
      (node (ref "T1") (pin "2") (pinfunction "E_2") (pintype "passive"))
      (node (ref "T2") (pin "2") (pinfunction "E_2") (pintype "passive"))
      (node (ref "T3") (pin "2") (pinfunction "E_2") (pintype "passive"))
      (node (ref "T4") (pin "2") (pinfunction "E_2") (pintype "passive"))
      (node (ref "T5") (pin "2") (pinfunction "E_2") (pintype "passive"))
      (node (ref "T6") (pin "2") (pinfunction "E_2") (pintype "passive"))
      (node (ref "T7") (pin "2") (pinfunction "E_2") (pintype "passive"))
      (node (ref "T8") (pin "2") (pinfunction "E_2") (pintype "passive"))
      (node (ref "TP27") (pin "P$1") (pinfunction "P$1_P$1") (pintype "bidirectional"))
      (node (ref "U$1") (pin "AGND") (pinfunction "AGND_AGND") (pintype "power_in"))
      (node (ref "X1") (pin "2") (pinfunction "2_2") (pintype "passive"))
      (node (ref "X2") (pin "2") (pinfunction "2_2") (pintype "passive"))
      (node (ref "X3") (pin "2") (pinfunction "2_2") (pintype "passive"))
      (node (ref "X4") (pin "2") (pinfunction "2_2") (pintype "passive"))
      (node (ref "X5") (pin "2") (pinfunction "2_2") (pintype "passive"))
      (node (ref "X6") (pin "2") (pinfunction "2_2") (pintype "passive"))
      (node (ref "X7") (pin "2") (pinfunction "2_2") (pintype "passive"))
      (node (ref "X8") (pin "2") (pinfunction "2_2") (pintype "passive"))
    )
    (net (code "12") (name "CS_DAC") (class "Default")
      (node (ref "IC3") (pin "6") (pinfunction "SYNC_6") (pintype "bidirectional"))
      (node (ref "U$1") (pin "6") (pinfunction "6/PWM_6") (pintype "bidirectional"))
    )
    (net (code "13") (name "CS_LCD") (class "Default")
      (node (ref "LCD_HEADER") (pin "6") (pinfunction "6_6") (pintype "passive"))
      (node (ref "U$1") (pin "12") (pinfunction "12/MISO_12") (pintype "bidirectional"))
    )
    (net (code "14") (name "CS_POT1") (class "Default")
      (node (ref "IC4") (pin "9") (pinfunction "CS_9") (pintype "bidirectional"))
      (node (ref "U$1") (pin "2") (pinfunction "2_2") (pintype "bidirectional"))
    )
    (net (code "15") (name "CS_POT2") (class "Default")
      (node (ref "IC5") (pin "9") (pinfunction "CS_9") (pintype "bidirectional"))
      (node (ref "U$1") (pin "3") (pinfunction "3/CAN-TX/PWM_3") (pintype "bidirectional"))
    )
    (net (code "16") (name "CS_POT3") (class "Default")
      (node (ref "IC8") (pin "9") (pinfunction "CS_9") (pintype "bidirectional"))
      (node (ref "U$1") (pin "4") (pinfunction "4/CAN-RX-PWM_4") (pintype "bidirectional"))
    )
    (net (code "17") (name "CS_POT4") (class "Default")
      (node (ref "IC10") (pin "9") (pinfunction "CS_9") (pintype "bidirectional"))
      (node (ref "U$1") (pin "5") (pinfunction "5/PWM_5") (pintype "bidirectional"))
    )
    (net (code "18") (name "ENC_A1") (class "Default")
      (node (ref "C17") (pin "2") (pinfunction "2_2") (pintype "passive"))
      (node (ref "ENC1") (pin "A") (pinfunction "A_A") (pintype "bidirectional"))
      (node (ref "R28") (pin "P$1") (pinfunction "1_P$1") (pintype "passive"))
      (node (ref "U$1") (pin "17/A3") (pinfunction "17/A3/T_17/A3") (pintype "bidirectional"))
    )
    (net (code "19") (name "ENC_A2") (class "Default")
      (node (ref "C19") (pin "2") (pinfunction "2_2") (pintype "passive"))
      (node (ref "ENC2") (pin "A") (pinfunction "A_A") (pintype "bidirectional"))
      (node (ref "R33") (pin "P$1") (pinfunction "1_P$1") (pintype "passive"))
      (node (ref "U$1") (pin "14/A0") (pinfunction "14/A0_14/A0") (pintype "bidirectional"))
    )
    (net (code "20") (name "ENC_B1") (class "Default")
      (node (ref "C16") (pin "2") (pinfunction "2_2") (pintype "passive"))
      (node (ref "ENC1") (pin "B") (pinfunction "B_B") (pintype "bidirectional"))
      (node (ref "R19") (pin "1") (pinfunction "P$1_1") (pintype "passive"))
      (node (ref "U$1") (pin "7") (pinfunction "7/RX3_7") (pintype "bidirectional"))
    )
    (net (code "21") (name "ENC_B2") (class "Default")
      (node (ref "C18") (pin "2") (pinfunction "2_2") (pintype "passive"))
      (node (ref "ENC2") (pin "B") (pinfunction "B_B") (pintype "bidirectional"))
      (node (ref "R32") (pin "1") (pinfunction "P$1_1") (pintype "passive"))
      (node (ref "U$1") (pin "16/A2") (pinfunction "16/A2/T_16/A2") (pintype "bidirectional"))
    )
    (net (code "22") (name "ENC_SW1") (class "Default")
      (node (ref "ENC1") (pin "E") (pinfunction "E_E") (pintype "bidirectional"))
      (node (ref "R29") (pin "1") (pinfunction "P$1_1") (pintype "passive"))
      (node (ref "U$1") (pin "8") (pinfunction "8/TX3_8") (pintype "bidirectional"))
    )
    (net (code "23") (name "ENC_SW2") (class "Default")
      (node (ref "ENC2") (pin "E") (pinfunction "E_E") (pintype "bidirectional"))
      (node (ref "R34") (pin "1") (pinfunction "P$1_1") (pintype "passive"))
      (node (ref "U$1") (pin "15/A1") (pinfunction "15/A1/T_15/A1") (pintype "bidirectional"))
    )
    (net (code "24") (name "GND") (class "Default")
      (node (ref "C1") (pin "1") (pinfunction "P$1_1") (pintype "passive"))
      (node (ref "C16") (pin "1") (pinfunction "1_1") (pintype "passive"))
      (node (ref "C17") (pin "1") (pinfunction "1_1") (pintype "passive"))
      (node (ref "C18") (pin "1") (pinfunction "1_1") (pintype "passive"))
      (node (ref "C19") (pin "1") (pinfunction "1_1") (pintype "passive"))
      (node (ref "C2") (pin "1") (pinfunction "P$1_1") (pintype "passive"))
      (node (ref "IC10") (pin "12") (pinfunction "VSS_12") (pintype "power_in"))
      (node (ref "IC4") (pin "12") (pinfunction "VSS_12") (pintype "power_in"))
      (node (ref "IC5") (pin "12") (pinfunction "VSS_12") (pintype "power_in"))
      (node (ref "IC8") (pin "12") (pinfunction "VSS_12") (pintype "power_in"))
      (node (ref "L3") (pin "2") (pinfunction "P$2_2") (pintype "passive"))
      (node (ref "LCD_HEADER") (pin "2") (pinfunction "2_2") (pintype "passive"))
      (node (ref "LCD_HEADER") (pin "4") (pinfunction "4_4") (pintype "passive"))
      (node (ref "R30") (pin "1") (pinfunction "P$1_1") (pintype "passive"))
      (node (ref "R31") (pin "1") (pinfunction "P$1_1") (pintype "passive"))
      (node (ref "R35") (pin "1") (pinfunction "P$1_1") (pintype "passive"))
      (node (ref "R36") (pin "1") (pinfunction "P$1_1") (pintype "passive"))
      (node (ref "U$1") (pin "GND") (pinfunction "GND_GND") (pintype "power_in"))
      (node (ref "U$1") (pin "GND1") (pinfunction "GND_GND1") (pintype "power_in"))
    )
    (net (code "25") (name "I1") (class "Default")
      (node (ref "IC4") (pin "16") (pinfunction "A2_16") (pintype "bidirectional"))
      (node (ref "JP1") (pin "5") (pinfunction "5_5") (pintype "passive"))
      (node (ref "TP6") (pin "P$1") (pinfunction "P$1_P$1") (pintype "bidirectional"))
    )
    (net (code "26") (name "I2") (class "Default")
      (node (ref "IC5") (pin "16") (pinfunction "A2_16") (pintype "bidirectional"))
      (node (ref "JP2") (pin "5") (pinfunction "5_5") (pintype "passive"))
      (node (ref "TP13") (pin "P$1") (pinfunction "P$1_P$1") (pintype "bidirectional"))
    )
    (net (code "27") (name "I3") (class "Default")
      (node (ref "IC8") (pin "16") (pinfunction "A2_16") (pintype "bidirectional"))
      (node (ref "JP8") (pin "5") (pinfunction "5_5") (pintype "passive"))
      (node (ref "TP19") (pin "P$1") (pinfunction "P$1_P$1") (pintype "bidirectional"))
    )
    (net (code "28") (name "I4") (class "Default")
      (node (ref "IC10") (pin "16") (pinfunction "A2_16") (pintype "bidirectional"))
      (node (ref "JP11") (pin "5") (pinfunction "5_5") (pintype "passive"))
      (node (ref "TP25") (pin "P$1") (pinfunction "P$1_P$1") (pintype "bidirectional"))
    )
    (net (code "29") (name "LIMA1") (class "Default")
      (node (ref "JP1") (pin "4") (pinfunction "4_4") (pintype "passive"))
      (node (ref "R2") (pin "2") (pinfunction "P$2_2") (pintype "passive"))
      (node (ref "T1") (pin "3") (pinfunction "C_3") (pintype "passive"))
    )
    (net (code "30") (name "LIMA2") (class "Default")
      (node (ref "JP2") (pin "4") (pinfunction "4_4") (pintype "passive"))
      (node (ref "R38") (pin "2") (pinfunction "P$2_2") (pintype "passive"))
      (node (ref "T3") (pin "3") (pinfunction "C_3") (pintype "passive"))
    )
    (net (code "31") (name "LIMA3") (class "Default")
      (node (ref "JP8") (pin "4") (pinfunction "4_4") (pintype "passive"))
      (node (ref "R56") (pin "2") (pinfunction "P$2_2") (pintype "passive"))
      (node (ref "T5") (pin "3") (pinfunction "C_3") (pintype "passive"))
    )
    (net (code "32") (name "LIMA4") (class "Default")
      (node (ref "JP11") (pin "4") (pinfunction "4_4") (pintype "passive"))
      (node (ref "R74") (pin "2") (pinfunction "P$2_2") (pintype "passive"))
      (node (ref "T7") (pin "3") (pinfunction "C_3") (pintype "passive"))
    )
    (net (code "33") (name "LIMB1") (class "Default")
      (node (ref "JP1") (pin "6") (pinfunction "6_6") (pintype "passive"))
      (node (ref "R4") (pin "2") (pinfunction "P$2_2") (pintype "passive"))
      (node (ref "T2") (pin "3") (pinfunction "C_3") (pintype "passive"))
    )
    (net (code "34") (name "LIMB2") (class "Default")
      (node (ref "JP2") (pin "6") (pinfunction "6_6") (pintype "passive"))
      (node (ref "R40") (pin "2") (pinfunction "P$2_2") (pintype "passive"))
      (node (ref "T4") (pin "3") (pinfunction "C_3") (pintype "passive"))
    )
    (net (code "35") (name "LIMB3") (class "Default")
      (node (ref "JP8") (pin "6") (pinfunction "6_6") (pintype "passive"))
      (node (ref "R58") (pin "2") (pinfunction "P$2_2") (pintype "passive"))
      (node (ref "T6") (pin "3") (pinfunction "C_3") (pintype "passive"))
    )
    (net (code "36") (name "LIMB4") (class "Default")
      (node (ref "JP11") (pin "6") (pinfunction "6_6") (pintype "passive"))
      (node (ref "R76") (pin "2") (pinfunction "P$2_2") (pintype "passive"))
      (node (ref "T8") (pin "3") (pinfunction "C_3") (pintype "passive"))
    )
    (net (code "37") (name "MOSI") (class "Default")
      (node (ref "LCD_HEADER") (pin "3") (pinfunction "3_3") (pintype "passive"))
      (node (ref "U$1") (pin "11") (pinfunction "11/MOSI_11") (pintype "bidirectional"))
    )
    (net (code "38") (name "MOSI_B") (class "Default")
      (node (ref "IC10") (pin "8") (pinfunction "SDI_8") (pintype "bidirectional"))
      (node (ref "IC3") (pin "8") (pinfunction "DIN_8") (pintype "bidirectional"))
      (node (ref "IC4") (pin "8") (pinfunction "SDI_8") (pintype "bidirectional"))
      (node (ref "IC5") (pin "8") (pinfunction "SDI_8") (pintype "bidirectional"))
      (node (ref "IC8") (pin "8") (pinfunction "SDI_8") (pintype "bidirectional"))
      (node (ref "U$1") (pin "0") (pinfunction "0/RX1/T_0") (pintype "bidirectional"))
    )
    (net (code "39") (name "Net-(C1-P$2)") (class "Default")
      (node (ref "C1") (pin "2") (pinfunction "P$2_2") (pintype "passive"))
      (node (ref "C2") (pin "2") (pinfunction "P$2_2") (pintype "passive"))
      (node (ref "L2") (pin "1") (pinfunction "P$1_1") (pintype "passive"))
      (node (ref "U$1") (pin "VIN") (pinfunction "VIN_VIN") (pintype "power_in"))
    )
    (net (code "40") (name "Net-(C27-P$2)") (class "Default")
      (node (ref "C27") (pin "2") (pinfunction "P$2_2") (pintype "passive"))
      (node (ref "C30") (pin "2") (pinfunction "P$2_2") (pintype "passive"))
      (node (ref "IC3") (pin "9") (pinfunction "VDD_9") (pintype "power_in"))
      (node (ref "L1") (pin "1") (pinfunction "P$1_1") (pintype "passive"))
    )
    (net (code "41") (name "Net-(ENC1-GND)") (class "Default")
      (node (ref "ENC1") (pin "C") (pinfunction "GND_C") (pintype "bidirectional"))
      (node (ref "R30") (pin "2") (pinfunction "P$2_2") (pintype "passive"))
    )
    (net (code "42") (name "Net-(ENC2-GND)") (class "Default")
      (node (ref "ENC2") (pin "C") (pinfunction "GND_C") (pintype "bidirectional"))
      (node (ref "R35") (pin "2") (pinfunction "P$2_2") (pintype "passive"))
    )
    (net (code "43") (name "Net-(IC1A--IN)") (class "Default")
      (node (ref "IC1") (pin "2") (pinfunction "-IN_2") (pintype "input"))
      (node (ref "R6") (pin "P$1") (pinfunction "1_P$1") (pintype "passive"))
      (node (ref "R8") (pin "1") (pinfunction "P$1_1") (pintype "passive"))
      (node (ref "TP2") (pin "P$1") (pinfunction "P$1_P$1") (pintype "bidirectional"))
    )
    (net (code "44") (name "Net-(IC1A-OUT)") (class "Default")
      (node (ref "IC1") (pin "1") (pinfunction "OUT_1") (pintype "output"))
      (node (ref "R10") (pin "2") (pinfunction "P$2_2") (pintype "passive"))
      (node (ref "R9") (pin "1") (pinfunction "P$1_1") (pintype "passive"))
    )
    (net (code "45") (name "Net-(IC1B-+IN)") (class "Default")
      (node (ref "IC1") (pin "5") (pinfunction "+IN_5") (pintype "input"))
      (node (ref "R11") (pin "1") (pinfunction "P$1_1") (pintype "passive"))
      (node (ref "R7") (pin "P$1") (pinfunction "1_P$1") (pintype "passive"))
      (node (ref "TP3") (pin "P$1") (pinfunction "P$1_P$1") (pintype "bidirectional"))
    )
    (net (code "46") (name "Net-(IC1B-OUT)") (class "Default")
      (node (ref "IC1") (pin "7") (pinfunction "OUT_7") (pintype "output"))
      (node (ref "R12") (pin "1") (pinfunction "P$1_1") (pintype "passive"))
      (node (ref "R13") (pin "2") (pinfunction "P$2_2") (pintype "passive"))
    )
    (net (code "47") (name "Net-(IC2A--IN)") (class "Default")
      (node (ref "IC2") (pin "2") (pinfunction "-IN_2") (pintype "input"))
      (node (ref "R41") (pin "P$1") (pinfunction "1_P$1") (pintype "passive"))
      (node (ref "R43") (pin "1") (pinfunction "P$1_1") (pintype "passive"))
      (node (ref "TP9") (pin "P$1") (pinfunction "P$1_P$1") (pintype "bidirectional"))
    )
    (net (code "48") (name "Net-(IC2A-OUT)") (class "Default")
      (node (ref "IC2") (pin "1") (pinfunction "OUT_1") (pintype "output"))
      (node (ref "R44") (pin "1") (pinfunction "P$1_1") (pintype "passive"))
      (node (ref "R45") (pin "2") (pinfunction "P$2_2") (pintype "passive"))
    )
    (net (code "49") (name "Net-(IC2B-+IN)") (class "Default")
      (node (ref "IC2") (pin "5") (pinfunction "+IN_5") (pintype "input"))
      (node (ref "R42") (pin "P$1") (pinfunction "1_P$1") (pintype "passive"))
      (node (ref "R46") (pin "1") (pinfunction "P$1_1") (pintype "passive"))
      (node (ref "TP10") (pin "P$1") (pinfunction "P$1_P$1") (pintype "bidirectional"))
    )
    (net (code "50") (name "Net-(IC2B-OUT)") (class "Default")
      (node (ref "IC2") (pin "7") (pinfunction "OUT_7") (pintype "output"))
      (node (ref "R47") (pin "1") (pinfunction "P$1_1") (pintype "passive"))
      (node (ref "R48") (pin "2") (pinfunction "P$2_2") (pintype "passive"))
    )
    (net (code "51") (name "Net-(IC3-VREF)") (class "Default")
      (node (ref "IC3") (pin "10") (pinfunction "VREF_10") (pintype "bidirectional"))
      (node (ref "JP14") (pin "1") (pinfunction "1_1") (pintype "passive"))
      (node (ref "TP1") (pin "P$1") (pinfunction "P$1_P$1") (pintype "bidirectional"))
    )
    (net (code "52") (name "Net-(IC7A--IN)") (class "Default")
      (node (ref "IC7") (pin "2") (pinfunction "-IN_2") (pintype "input"))
      (node (ref "R59") (pin "P$1") (pinfunction "1_P$1") (pintype "passive"))
      (node (ref "R61") (pin "1") (pinfunction "P$1_1") (pintype "passive"))
      (node (ref "TP15") (pin "P$1") (pinfunction "P$1_P$1") (pintype "bidirectional"))
    )
    (net (code "53") (name "Net-(IC7A-OUT)") (class "Default")
      (node (ref "IC7") (pin "1") (pinfunction "OUT_1") (pintype "output"))
      (node (ref "R62") (pin "1") (pinfunction "P$1_1") (pintype "passive"))
      (node (ref "R63") (pin "2") (pinfunction "P$2_2") (pintype "passive"))
    )
    (net (code "54") (name "Net-(IC7B-+IN)") (class "Default")
      (node (ref "IC7") (pin "5") (pinfunction "+IN_5") (pintype "input"))
      (node (ref "R60") (pin "P$1") (pinfunction "1_P$1") (pintype "passive"))
      (node (ref "R64") (pin "1") (pinfunction "P$1_1") (pintype "passive"))
      (node (ref "TP16") (pin "P$1") (pinfunction "P$1_P$1") (pintype "bidirectional"))
    )
    (net (code "55") (name "Net-(IC7B-OUT)") (class "Default")
      (node (ref "IC7") (pin "7") (pinfunction "OUT_7") (pintype "output"))
      (node (ref "R65") (pin "1") (pinfunction "P$1_1") (pintype "passive"))
      (node (ref "R66") (pin "2") (pinfunction "P$2_2") (pintype "passive"))
    )
    (net (code "56") (name "Net-(IC9A--IN)") (class "Default")
      (node (ref "IC9") (pin "2") (pinfunction "-IN_2") (pintype "input"))
      (node (ref "R77") (pin "P$1") (pinfunction "1_P$1") (pintype "passive"))
      (node (ref "R79") (pin "1") (pinfunction "P$1_1") (pintype "passive"))
      (node (ref "TP21") (pin "P$1") (pinfunction "P$1_P$1") (pintype "bidirectional"))
    )
    (net (code "57") (name "Net-(IC9A-OUT)") (class "Default")
      (node (ref "IC9") (pin "1") (pinfunction "OUT_1") (pintype "output"))
      (node (ref "R80") (pin "1") (pinfunction "P$1_1") (pintype "passive"))
      (node (ref "R81") (pin "2") (pinfunction "P$2_2") (pintype "passive"))
    )
    (net (code "58") (name "Net-(IC9B-+IN)") (class "Default")
      (node (ref "IC9") (pin "5") (pinfunction "+IN_5") (pintype "input"))
      (node (ref "R78") (pin "P$1") (pinfunction "1_P$1") (pintype "passive"))
      (node (ref "R82") (pin "1") (pinfunction "P$1_1") (pintype "passive"))
      (node (ref "TP22") (pin "P$1") (pinfunction "P$1_P$1") (pintype "bidirectional"))
    )
    (net (code "59") (name "Net-(IC9B-OUT)") (class "Default")
      (node (ref "IC9") (pin "7") (pinfunction "OUT_7") (pintype "output"))
      (node (ref "R83") (pin "1") (pinfunction "P$1_1") (pintype "passive"))
      (node (ref "R84") (pin "2") (pinfunction "P$2_2") (pintype "passive"))
    )
    (net (code "60") (name "Net-(LCD_HEADER-Pad1)") (class "Default")
      (node (ref "LCD_HEADER") (pin "1") (pinfunction "1_1") (pintype "passive"))
      (node (ref "U$1") (pin "3.3V") (pinfunction "3.3V_3.3V") (pintype "power_in"))
      (node (ref "U$1") (pin "3.3V1") (pinfunction "3.3V_3.3V1") (pintype "power_in"))
    )
    (net (code "61") (name "Net-(R1-P$2)") (class "Default")
      (node (ref "JP3") (pin "1") (pinfunction "1_1") (pintype "passive"))
      (node (ref "R1") (pin "2") (pinfunction "P$2_2") (pintype "passive"))
      (node (ref "R2") (pin "1") (pinfunction "P$1_1") (pintype "passive"))
      (node (ref "S1") (pin "P$3") (pinfunction "3_P$3") (pintype "bidirectional"))
    )
    (net (code "62") (name "Net-(R3-P$2)") (class "Default")
      (node (ref "JP5") (pin "1") (pinfunction "1_1") (pintype "passive"))
      (node (ref "R3") (pin "2") (pinfunction "P$2_2") (pintype "passive"))
      (node (ref "R4") (pin "1") (pinfunction "P$1_1") (pintype "passive"))
      (node (ref "S1") (pin "P$6") (pinfunction "6_P$6") (pintype "bidirectional"))
    )
    (net (code "63") (name "Net-(R5-P$1)") (class "Default")
      (node (ref "R5") (pin "1") (pinfunction "P$1_1") (pintype "passive"))
      (node (ref "S1") (pin "P$4") (pinfunction "4_P$4") (pintype "bidirectional"))
    )
    (net (code "64") (name "Net-(R5-P$2)") (class "Default")
      (node (ref "D1") (pin "C") (pinfunction "C_C") (pintype "bidirectional"))
      (node (ref "R5") (pin "2") (pinfunction "P$2_2") (pintype "passive"))
    )
    (net (code "65") (name "Net-(R10-P$1)") (class "Default")
      (node (ref "R10") (pin "1") (pinfunction "P$1_1") (pintype "passive"))
      (node (ref "T1") (pin "1") (pinfunction "B_1") (pintype "passive"))
    )
    (net (code "66") (name "Net-(R13-P$1)") (class "Default")
      (node (ref "R13") (pin "1") (pinfunction "P$1_1") (pintype "passive"))
      (node (ref "T2") (pin "1") (pinfunction "B_1") (pintype "passive"))
    )
    (net (code "67") (name "Net-(R14-P$1)") (class "Default")
      (node (ref "JP1") (pin "8") (pinfunction "8_8") (pintype "passive"))
      (node (ref "R14") (pin "1") (pinfunction "P$1_1") (pintype "passive"))
      (node (ref "R15") (pin "1") (pinfunction "P$1_1") (pintype "passive"))
    )
    (net (code "68") (name "Net-(R14-P$2)") (class "Default")
      (node (ref "R14") (pin "2") (pinfunction "P$2_2") (pintype "passive"))
      (node (ref "X1") (pin "1") (pinfunction "1_1") (pintype "passive"))
    )
    (net (code "69") (name "Net-(R18-P$2)") (class "Default")
      (node (ref "R18") (pin "2") (pinfunction "P$2_2") (pintype "passive"))
      (node (ref "X2") (pin "1") (pinfunction "1_1") (pintype "passive"))
    )
    (net (code "70") (name "Net-(R31-P$2)") (class "Default")
      (node (ref "ENC1") (pin "D") (pinfunction "D_D") (pintype "bidirectional"))
      (node (ref "R31") (pin "2") (pinfunction "P$2_2") (pintype "passive"))
    )
    (net (code "71") (name "Net-(R36-P$2)") (class "Default")
      (node (ref "ENC2") (pin "D") (pinfunction "D_D") (pintype "bidirectional"))
      (node (ref "R36") (pin "2") (pinfunction "P$2_2") (pintype "passive"))
    )
    (net (code "72") (name "Net-(R37-P$2)") (class "Default")
      (node (ref "JP6") (pin "1") (pinfunction "1_1") (pintype "passive"))
      (node (ref "R37") (pin "2") (pinfunction "P$2_2") (pintype "passive"))
      (node (ref "R38") (pin "1") (pinfunction "P$1_1") (pintype "passive"))
      (node (ref "S2") (pin "P$3") (pinfunction "3_P$3") (pintype "bidirectional"))
    )
    (net (code "73") (name "Net-(R39-P$2)") (class "Default")
      (node (ref "JP7") (pin "1") (pinfunction "1_1") (pintype "passive"))
      (node (ref "R39") (pin "2") (pinfunction "P$2_2") (pintype "passive"))
      (node (ref "R40") (pin "1") (pinfunction "P$1_1") (pintype "passive"))
      (node (ref "S2") (pin "P$6") (pinfunction "6_P$6") (pintype "bidirectional"))
    )
    (net (code "74") (name "Net-(R45-P$1)") (class "Default")
      (node (ref "R45") (pin "1") (pinfunction "P$1_1") (pintype "passive"))
      (node (ref "T3") (pin "1") (pinfunction "B_1") (pintype "passive"))
    )
    (net (code "75") (name "Net-(R48-P$1)") (class "Default")
      (node (ref "R48") (pin "1") (pinfunction "P$1_1") (pintype "passive"))
      (node (ref "T4") (pin "1") (pinfunction "B_1") (pintype "passive"))
    )
    (net (code "76") (name "Net-(R49-P$1)") (class "Default")
      (node (ref "R49") (pin "1") (pinfunction "P$1_1") (pintype "passive"))
      (node (ref "S2") (pin "P$4") (pinfunction "4_P$4") (pintype "bidirectional"))
    )
    (net (code "77") (name "Net-(R49-P$2)") (class "Default")
      (node (ref "D2") (pin "C") (pinfunction "C_C") (pintype "bidirectional"))
      (node (ref "R49") (pin "2") (pinfunction "P$2_2") (pintype "passive"))
    )
    (net (code "78") (name "Net-(R52-P$1)") (class "Default")
      (node (ref "JP2") (pin "8") (pinfunction "8_8") (pintype "passive"))
      (node (ref "R52") (pin "1") (pinfunction "P$1_1") (pintype "passive"))
      (node (ref "R53") (pin "1") (pinfunction "P$1_1") (pintype "passive"))
    )
    (net (code "79") (name "Net-(R52-P$2)") (class "Default")
      (node (ref "R52") (pin "2") (pinfunction "P$2_2") (pintype "passive"))
      (node (ref "X3") (pin "1") (pinfunction "1_1") (pintype "passive"))
    )
    (net (code "80") (name "Net-(R54-P$2)") (class "Default")
      (node (ref "R54") (pin "2") (pinfunction "P$2_2") (pintype "passive"))
      (node (ref "X4") (pin "1") (pinfunction "1_1") (pintype "passive"))
    )
    (net (code "81") (name "Net-(R55-P$2)") (class "Default")
      (node (ref "JP9") (pin "1") (pinfunction "1_1") (pintype "passive"))
      (node (ref "R55") (pin "2") (pinfunction "P$2_2") (pintype "passive"))
      (node (ref "R56") (pin "1") (pinfunction "P$1_1") (pintype "passive"))
      (node (ref "S3") (pin "P$3") (pinfunction "3_P$3") (pintype "bidirectional"))
    )
    (net (code "82") (name "Net-(R57-P$2)") (class "Default")
      (node (ref "JP10") (pin "1") (pinfunction "1_1") (pintype "passive"))
      (node (ref "R57") (pin "2") (pinfunction "P$2_2") (pintype "passive"))
      (node (ref "R58") (pin "1") (pinfunction "P$1_1") (pintype "passive"))
      (node (ref "S3") (pin "P$6") (pinfunction "6_P$6") (pintype "bidirectional"))
    )
    (net (code "83") (name "Net-(R63-P$1)") (class "Default")
      (node (ref "R63") (pin "1") (pinfunction "P$1_1") (pintype "passive"))
      (node (ref "T5") (pin "1") (pinfunction "B_1") (pintype "passive"))
    )
    (net (code "84") (name "Net-(R66-P$1)") (class "Default")
      (node (ref "R66") (pin "1") (pinfunction "P$1_1") (pintype "passive"))
      (node (ref "T6") (pin "1") (pinfunction "B_1") (pintype "passive"))
    )
    (net (code "85") (name "Net-(R67-P$1)") (class "Default")
      (node (ref "R67") (pin "1") (pinfunction "P$1_1") (pintype "passive"))
      (node (ref "S3") (pin "P$4") (pinfunction "4_P$4") (pintype "bidirectional"))
    )
    (net (code "86") (name "Net-(R67-P$2)") (class "Default")
      (node (ref "D3") (pin "C") (pinfunction "C_C") (pintype "bidirectional"))
      (node (ref "R67") (pin "2") (pinfunction "P$2_2") (pintype "passive"))
    )
    (net (code "87") (name "Net-(R70-P$1)") (class "Default")
      (node (ref "JP8") (pin "8") (pinfunction "8_8") (pintype "passive"))
      (node (ref "R70") (pin "1") (pinfunction "P$1_1") (pintype "passive"))
      (node (ref "R71") (pin "1") (pinfunction "P$1_1") (pintype "passive"))
    )
    (net (code "88") (name "Net-(R70-P$2)") (class "Default")
      (node (ref "R70") (pin "2") (pinfunction "P$2_2") (pintype "passive"))
      (node (ref "X5") (pin "1") (pinfunction "1_1") (pintype "passive"))
    )
    (net (code "89") (name "Net-(R72-P$2)") (class "Default")
      (node (ref "R72") (pin "2") (pinfunction "P$2_2") (pintype "passive"))
      (node (ref "X6") (pin "1") (pinfunction "1_1") (pintype "passive"))
    )
    (net (code "90") (name "Net-(R73-P$2)") (class "Default")
      (node (ref "JP12") (pin "1") (pinfunction "1_1") (pintype "passive"))
      (node (ref "R73") (pin "2") (pinfunction "P$2_2") (pintype "passive"))
      (node (ref "R74") (pin "1") (pinfunction "P$1_1") (pintype "passive"))
      (node (ref "S4") (pin "P$3") (pinfunction "3_P$3") (pintype "bidirectional"))
    )
    (net (code "91") (name "Net-(R75-P$2)") (class "Default")
      (node (ref "JP13") (pin "1") (pinfunction "1_1") (pintype "passive"))
      (node (ref "R75") (pin "2") (pinfunction "P$2_2") (pintype "passive"))
      (node (ref "R76") (pin "1") (pinfunction "P$1_1") (pintype "passive"))
      (node (ref "S4") (pin "P$6") (pinfunction "6_P$6") (pintype "bidirectional"))
    )
    (net (code "92") (name "Net-(R81-P$1)") (class "Default")
      (node (ref "R81") (pin "1") (pinfunction "P$1_1") (pintype "passive"))
      (node (ref "T7") (pin "1") (pinfunction "B_1") (pintype "passive"))
    )
    (net (code "93") (name "Net-(R84-P$1)") (class "Default")
      (node (ref "R84") (pin "1") (pinfunction "P$1_1") (pintype "passive"))
      (node (ref "T8") (pin "1") (pinfunction "B_1") (pintype "passive"))
    )
    (net (code "94") (name "Net-(R85-P$1)") (class "Default")
      (node (ref "R85") (pin "1") (pinfunction "P$1_1") (pintype "passive"))
      (node (ref "S4") (pin "P$4") (pinfunction "4_P$4") (pintype "bidirectional"))
    )
    (net (code "95") (name "Net-(R85-P$2)") (class "Default")
      (node (ref "D4") (pin "C") (pinfunction "C_C") (pintype "bidirectional"))
      (node (ref "R85") (pin "2") (pinfunction "P$2_2") (pintype "passive"))
    )
    (net (code "96") (name "Net-(R88-P$1)") (class "Default")
      (node (ref "JP11") (pin "8") (pinfunction "8_8") (pintype "passive"))
      (node (ref "R88") (pin "1") (pinfunction "P$1_1") (pintype "passive"))
      (node (ref "R89") (pin "1") (pinfunction "P$1_1") (pintype "passive"))
    )
    (net (code "97") (name "Net-(R88-P$2)") (class "Default")
      (node (ref "R88") (pin "2") (pinfunction "P$2_2") (pintype "passive"))
      (node (ref "X7") (pin "1") (pinfunction "1_1") (pintype "passive"))
    )
    (net (code "98") (name "Net-(R90-P$2)") (class "Default")
      (node (ref "R90") (pin "2") (pinfunction "P$2_2") (pintype "passive"))
      (node (ref "X8") (pin "1") (pinfunction "1_1") (pintype "passive"))
    )
    (net (code "99") (name "P1") (class "Default")
      (node (ref "IC4") (pin "2") (pinfunction "A1_2") (pintype "bidirectional"))
      (node (ref "JP1") (pin "1") (pinfunction "1_1") (pintype "passive"))
      (node (ref "TP4") (pin "P$1") (pinfunction "P$1_P$1") (pintype "bidirectional"))
    )
    (net (code "100") (name "P2") (class "Default")
      (node (ref "IC5") (pin "2") (pinfunction "A1_2") (pintype "bidirectional"))
      (node (ref "JP2") (pin "1") (pinfunction "1_1") (pintype "passive"))
      (node (ref "TP11") (pin "P$1") (pinfunction "P$1_P$1") (pintype "bidirectional"))
    )
    (net (code "101") (name "P3") (class "Default")
      (node (ref "IC8") (pin "2") (pinfunction "A1_2") (pintype "bidirectional"))
      (node (ref "JP8") (pin "1") (pinfunction "1_1") (pintype "passive"))
      (node (ref "TP17") (pin "P$1") (pinfunction "P$1_P$1") (pintype "bidirectional"))
    )
    (net (code "102") (name "P4") (class "Default")
      (node (ref "IC10") (pin "2") (pinfunction "A1_2") (pintype "bidirectional"))
      (node (ref "JP11") (pin "1") (pinfunction "1_1") (pintype "passive"))
      (node (ref "TP23") (pin "P$1") (pinfunction "P$1_P$1") (pintype "bidirectional"))
    )
    (net (code "103") (name "RST_LCD") (class "Default")
      (node (ref "LCD_HEADER") (pin "8") (pinfunction "8_8") (pintype "passive"))
      (node (ref "U$1") (pin "9") (pinfunction "9/RX2/PWM_9") (pintype "bidirectional"))
    )
    (net (code "104") (name "RS_LCD") (class "Default")
      (node (ref "LCD_HEADER") (pin "7") (pinfunction "7_7") (pintype "passive"))
      (node (ref "U$1") (pin "10") (pinfunction "10/TX2/PWM_10") (pintype "bidirectional"))
    )
    (net (code "105") (name "SCK") (class "Default")
      (node (ref "LCD_HEADER") (pin "5") (pinfunction "5_5") (pintype "passive"))
      (node (ref "U$1") (pin "13") (pinfunction "13/SCK/LED_13") (pintype "bidirectional"))
    )
    (net (code "106") (name "SCK_B") (class "Default")
      (node (ref "IC10") (pin "7") (pinfunction "CLK_7") (pintype "bidirectional"))
      (node (ref "IC3") (pin "7") (pinfunction "SCLK_7") (pintype "bidirectional"))
      (node (ref "IC4") (pin "7") (pinfunction "CLK_7") (pintype "bidirectional"))
      (node (ref "IC5") (pin "7") (pinfunction "CLK_7") (pintype "bidirectional"))
      (node (ref "IC8") (pin "7") (pinfunction "CLK_7") (pintype "bidirectional"))
      (node (ref "U$1") (pin "1") (pinfunction "1/TX1/T_1") (pintype "bidirectional"))
    )
    (net (code "107") (name "VBAT") (class "Default")
      (node (ref "U$1") (pin "VBAT") (pinfunction "VBAT_VBAT") (pintype "power_in"))
    )
    (net (code "108") (name "VDD") (class "Default")
      (node (ref "C12") (pin "2") (pinfunction "P$2_2") (pintype "passive"))
      (node (ref "C13") (pin "2") (pinfunction "P$2_2") (pintype "passive"))
      (node (ref "C15") (pin "2") (pinfunction "P$2_2") (pintype "passive"))
      (node (ref "C20") (pin "2") (pinfunction "P$2_2") (pintype "passive"))
      (node (ref "C21") (pin "2") (pinfunction "P$2_2") (pintype "passive"))
      (node (ref "C22") (pin "2") (pinfunction "P$2_2") (pintype "passive"))
      (node (ref "C23") (pin "2") (pinfunction "P$2_2") (pintype "passive"))
      (node (ref "C24") (pin "2") (pinfunction "P$2_2") (pintype "passive"))
      (node (ref "C25") (pin "2") (pinfunction "P$2_2") (pintype "passive"))
      (node (ref "CP3") (pin "+") (pinfunction "+_+") (pintype "passive"))
      (node (ref "D1") (pin "A") (pinfunction "A_A") (pintype "bidirectional"))
      (node (ref "D2") (pin "A") (pinfunction "A_A") (pintype "bidirectional"))
      (node (ref "D3") (pin "A") (pinfunction "A_A") (pintype "bidirectional"))
      (node (ref "D4") (pin "A") (pinfunction "A_A") (pintype "bidirectional"))
      (node (ref "IC1") (pin "8") (pinfunction "V+_8") (pintype "power_in"))
      (node (ref "IC10") (pin "10") (pinfunction "PR_10") (pintype "bidirectional"))
      (node (ref "IC10") (pin "13") (pinfunction "VL_13") (pintype "power_in"))
      (node (ref "IC10") (pin "5") (pinfunction "VDD_5") (pintype "power_in"))
      (node (ref "IC10") (pin "6") (pinfunction "SHDN_6") (pintype "bidirectional"))
      (node (ref "IC2") (pin "8") (pinfunction "V+_8") (pintype "power_in"))
      (node (ref "IC4") (pin "10") (pinfunction "PR_10") (pintype "bidirectional"))
      (node (ref "IC4") (pin "13") (pinfunction "VL_13") (pintype "power_in"))
      (node (ref "IC4") (pin "5") (pinfunction "VDD_5") (pintype "power_in"))
      (node (ref "IC4") (pin "6") (pinfunction "SHDN_6") (pintype "bidirectional"))
      (node (ref "IC5") (pin "10") (pinfunction "PR_10") (pintype "bidirectional"))
      (node (ref "IC5") (pin "13") (pinfunction "VL_13") (pintype "power_in"))
      (node (ref "IC5") (pin "5") (pinfunction "VDD_5") (pintype "power_in"))
      (node (ref "IC5") (pin "6") (pinfunction "SHDN_6") (pintype "bidirectional"))
      (node (ref "IC6") (pin "1") (pinfunction "IN_1") (pintype "bidirectional"))
      (node (ref "IC7") (pin "8") (pinfunction "V+_8") (pintype "power_in"))
      (node (ref "IC8") (pin "10") (pinfunction "PR_10") (pintype "bidirectional"))
      (node (ref "IC8") (pin "13") (pinfunction "VL_13") (pintype "power_in"))
      (node (ref "IC8") (pin "5") (pinfunction "VDD_5") (pintype "power_in"))
      (node (ref "IC8") (pin "6") (pinfunction "SHDN_6") (pintype "bidirectional"))
      (node (ref "IC9") (pin "8") (pinfunction "V+_8") (pintype "power_in"))
      (node (ref "JP1") (pin "11") (pinfunction "11_11") (pintype "passive"))
      (node (ref "JP1") (pin "2") (pinfunction "2_2") (pintype "passive"))
      (node (ref "JP11") (pin "11") (pinfunction "11_11") (pintype "passive"))
      (node (ref "JP11") (pin "2") (pinfunction "2_2") (pintype "passive"))
      (node (ref "JP2") (pin "11") (pinfunction "11_11") (pintype "passive"))
      (node (ref "JP2") (pin "2") (pinfunction "2_2") (pintype "passive"))
      (node (ref "JP8") (pin "11") (pinfunction "11_11") (pintype "passive"))
      (node (ref "JP8") (pin "2") (pinfunction "2_2") (pintype "passive"))
      (node (ref "L1") (pin "2") (pinfunction "P$2_2") (pintype "passive"))
      (node (ref "L2") (pin "2") (pinfunction "P$2_2") (pintype "passive"))
      (node (ref "L4") (pin "1") (pinfunction "P$1_1") (pintype "passive"))
      (node (ref "R11") (pin "2") (pinfunction "P$2_2") (pintype "passive"))
      (node (ref "R12") (pin "2") (pinfunction "P$2_2") (pintype "passive"))
      (node (ref "R19") (pin "2") (pinfunction "P$2_2") (pintype "passive"))
      (node (ref "R28") (pin "P$2") (pinfunction "2_P$2") (pintype "passive"))
      (node (ref "R29") (pin "2") (pinfunction "P$2_2") (pintype "passive"))
      (node (ref "R32") (pin "2") (pinfunction "P$2_2") (pintype "passive"))
      (node (ref "R33") (pin "P$2") (pinfunction "2_P$2") (pintype "passive"))
      (node (ref "R34") (pin "2") (pinfunction "P$2_2") (pintype "passive"))
      (node (ref "R43") (pin "2") (pinfunction "P$2_2") (pintype "passive"))
      (node (ref "R44") (pin "2") (pinfunction "P$2_2") (pintype "passive"))
      (node (ref "R46") (pin "2") (pinfunction "P$2_2") (pintype "passive"))
      (node (ref "R47") (pin "2") (pinfunction "P$2_2") (pintype "passive"))
      (node (ref "R61") (pin "2") (pinfunction "P$2_2") (pintype "passive"))
      (node (ref "R62") (pin "2") (pinfunction "P$2_2") (pintype "passive"))
      (node (ref "R64") (pin "2") (pinfunction "P$2_2") (pintype "passive"))
      (node (ref "R65") (pin "2") (pinfunction "P$2_2") (pintype "passive"))
      (node (ref "R79") (pin "2") (pinfunction "P$2_2") (pintype "passive"))
      (node (ref "R8") (pin "2") (pinfunction "P$2_2") (pintype "passive"))
      (node (ref "R80") (pin "2") (pinfunction "P$2_2") (pintype "passive"))
      (node (ref "R82") (pin "2") (pinfunction "P$2_2") (pintype "passive"))
      (node (ref "R83") (pin "2") (pinfunction "P$2_2") (pintype "passive"))
      (node (ref "R9") (pin "2") (pinfunction "P$2_2") (pintype "passive"))
    )
    (net (code "109") (name "VMON1") (class "Default")
      (node (ref "JP1") (pin "7") (pinfunction "7_7") (pintype "passive"))
      (node (ref "R18") (pin "1") (pinfunction "P$1_1") (pintype "passive"))
      (node (ref "R26") (pin "P$2") (pinfunction "2_P$2") (pintype "passive"))
    )
    (net (code "110") (name "VMON1_B") (class "Default")
      (node (ref "C9") (pin "2") (pinfunction "P$2_2") (pintype "passive"))
      (node (ref "R26") (pin "P$1") (pinfunction "1_P$1") (pintype "passive"))
      (node (ref "R27") (pin "P$2") (pinfunction "2_P$2") (pintype "passive"))
      (node (ref "U$1") (pin "A10") (pinfunction "A10_A10") (pintype "bidirectional"))
    )
    (net (code "111") (name "VMON2") (class "Default")
      (node (ref "JP2") (pin "7") (pinfunction "7_7") (pintype "passive"))
      (node (ref "R24") (pin "P$2") (pinfunction "2_P$2") (pintype "passive"))
      (node (ref "R54") (pin "1") (pinfunction "P$1_1") (pintype "passive"))
    )
    (net (code "112") (name "VMON2_B") (class "Default")
      (node (ref "C6") (pin "2") (pinfunction "P$2_2") (pintype "passive"))
      (node (ref "R24") (pin "P$1") (pinfunction "1_P$1") (pintype "passive"))
      (node (ref "R25") (pin "P$2") (pinfunction "2_P$2") (pintype "passive"))
      (node (ref "U$1") (pin "22/A8") (pinfunction "22/A8/T/PWM_22/A8") (pintype "bidirectional"))
    )
    (net (code "113") (name "VMON3") (class "Default")
      (node (ref "JP8") (pin "7") (pinfunction "7_7") (pintype "passive"))
      (node (ref "R22") (pin "P$2") (pinfunction "2_P$2") (pintype "passive"))
      (node (ref "R72") (pin "1") (pinfunction "P$1_1") (pintype "passive"))
    )
    (net (code "114") (name "VMON3_B") (class "Default")
      (node (ref "C4") (pin "2") (pinfunction "P$2_2") (pintype "passive"))
      (node (ref "R22") (pin "P$1") (pinfunction "1_P$1") (pintype "passive"))
      (node (ref "R23") (pin "P$2") (pinfunction "2_P$2") (pintype "passive"))
      (node (ref "U$1") (pin "20/A6") (pinfunction "20/A6/PWM_20/A6") (pintype "bidirectional"))
    )
    (net (code "115") (name "VMON4") (class "Default")
      (node (ref "JP11") (pin "7") (pinfunction "7_7") (pintype "passive"))
      (node (ref "R20") (pin "P$2") (pinfunction "2_P$2") (pintype "passive"))
      (node (ref "R90") (pin "1") (pinfunction "P$1_1") (pintype "passive"))
    )
    (net (code "116") (name "VMON4_B") (class "Default")
      (node (ref "C3") (pin "2") (pinfunction "P$2_2") (pintype "passive"))
      (node (ref "R20") (pin "P$1") (pinfunction "1_P$1") (pintype "passive"))
      (node (ref "R21") (pin "P$2") (pinfunction "2_P$2") (pintype "passive"))
      (node (ref "U$1") (pin "18/A4") (pinfunction "18/A4/T/SDA0_18/A4") (pintype "bidirectional"))
    )
    (net (code "117") (name "VSET1") (class "Default")
      (node (ref "IC1") (pin "3") (pinfunction "+IN_3") (pintype "input"))
      (node (ref "IC1") (pin "6") (pinfunction "-IN_6") (pintype "input"))
      (node (ref "IC3") (pin "1") (pinfunction "VOUTA_1") (pintype "output"))
      (node (ref "JP1") (pin "10") (pinfunction "10_10") (pintype "passive"))
      (node (ref "TP8") (pin "P$1") (pinfunction "P$1_P$1") (pintype "bidirectional"))
    )
    (net (code "118") (name "VSET2") (class "Default")
      (node (ref "IC2") (pin "3") (pinfunction "+IN_3") (pintype "input"))
      (node (ref "IC2") (pin "6") (pinfunction "-IN_6") (pintype "input"))
      (node (ref "IC3") (pin "2") (pinfunction "VOUTB_2") (pintype "output"))
      (node (ref "JP2") (pin "10") (pinfunction "10_10") (pintype "passive"))
      (node (ref "TP14") (pin "P$1") (pinfunction "P$1_P$1") (pintype "bidirectional"))
    )
    (net (code "119") (name "VSET3") (class "Default")
      (node (ref "IC3") (pin "4") (pinfunction "VOUTC_4") (pintype "output"))
      (node (ref "IC7") (pin "3") (pinfunction "+IN_3") (pintype "input"))
      (node (ref "IC7") (pin "6") (pinfunction "-IN_6") (pintype "input"))
      (node (ref "JP8") (pin "10") (pinfunction "10_10") (pintype "passive"))
      (node (ref "TP20") (pin "P$1") (pinfunction "P$1_P$1") (pintype "bidirectional"))
    )
    (net (code "120") (name "VSET4") (class "Default")
      (node (ref "IC3") (pin "5") (pinfunction "VOUTD_5") (pintype "output"))
      (node (ref "IC9") (pin "3") (pinfunction "+IN_3") (pintype "input"))
      (node (ref "IC9") (pin "6") (pinfunction "-IN_6") (pintype "input"))
      (node (ref "JP11") (pin "10") (pinfunction "10_10") (pintype "passive"))
      (node (ref "TP26") (pin "P$1") (pinfunction "P$1_P$1") (pintype "bidirectional"))
    )
    (net (code "121") (name "VUSB") (class "Default")
      (node (ref "U$1") (pin "VUSB") (pinfunction "VUSB_VUSB") (pintype "power_in"))
    )
    (net (code "122") (name "unconnected-(IC4-SDO-Pad1)") (class "Default")
      (node (ref "IC4") (pin "1") (pinfunction "SDO_1") (pintype "bidirectional"))
    )
    (net (code "123") (name "unconnected-(IC5-SDO-Pad1)") (class "Default")
      (node (ref "IC5") (pin "1") (pinfunction "SDO_1") (pintype "bidirectional"))
    )
    (net (code "124") (name "unconnected-(IC8-SDO-Pad1)") (class "Default")
      (node (ref "IC8") (pin "1") (pinfunction "SDO_1") (pintype "bidirectional"))
    )
    (net (code "125") (name "unconnected-(IC10-SDO-Pad1)") (class "Default")
      (node (ref "IC10") (pin "1") (pinfunction "SDO_1") (pintype "bidirectional"))
    )
    (net (code "126") (name "unconnected-(S1-1-PadP$1)") (class "Default")
      (node (ref "S1") (pin "P$1") (pinfunction "1_P$1") (pintype "bidirectional"))
    )
    (net (code "127") (name "unconnected-(S2-1-PadP$1)") (class "Default")
      (node (ref "S2") (pin "P$1") (pinfunction "1_P$1") (pintype "bidirectional"))
    )
    (net (code "128") (name "unconnected-(S3-1-PadP$1)") (class "Default")
      (node (ref "S3") (pin "P$1") (pinfunction "1_P$1") (pintype "bidirectional"))
    )
    (net (code "129") (name "unconnected-(S4-1-PadP$1)") (class "Default")
      (node (ref "S4") (pin "P$1") (pinfunction "1_P$1") (pintype "bidirectional"))
    )
    (net (code "130") (name "unconnected-(U$1-A14{slash}DAC-PadA14)") (class "Default")
      (node (ref "U$1") (pin "A14") (pinfunction "A14/DAC_A14") (pintype "bidirectional"))
    )
    (net (code "131") (name "unconnected-(U$1-PadPGM)") (class "Default")
      (node (ref "U$1") (pin "PGM") (pinfunction "PGM_PGM") (pintype "bidirectional"))
    )
  )
)
